# musical-plant.net
KiCad netlist of a schematic drawn in EAGLE
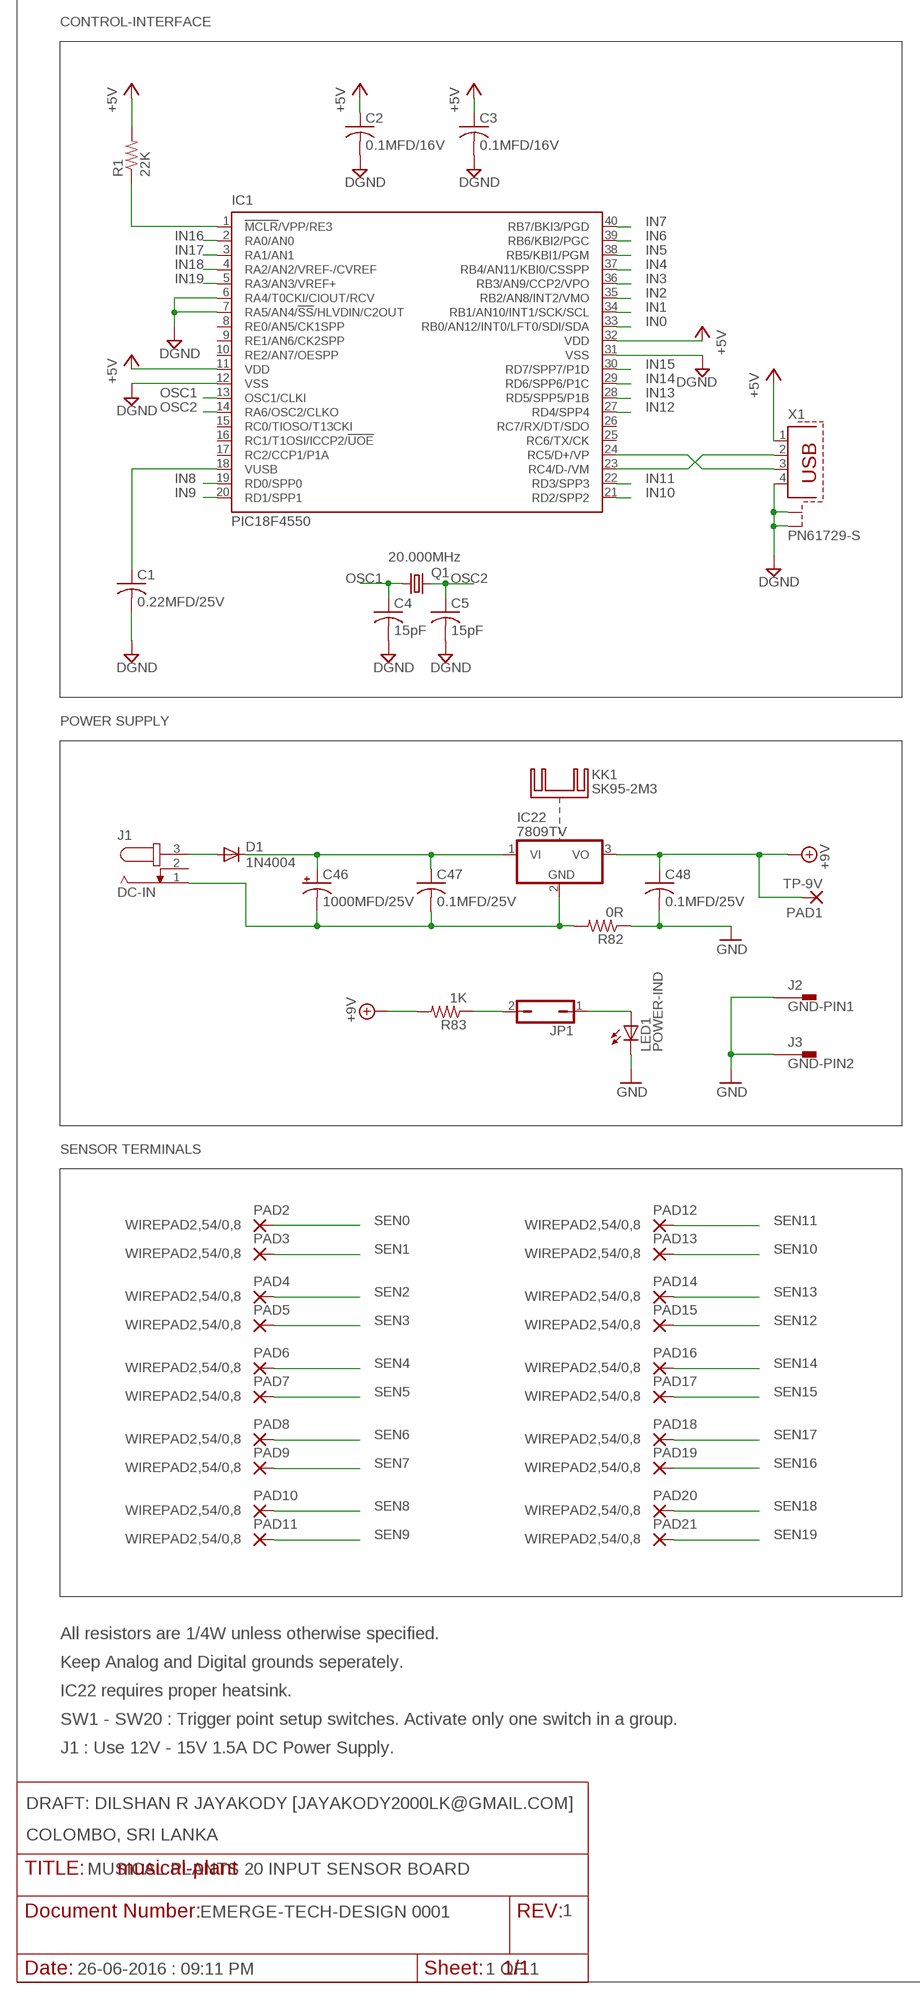
[diagram p0: schematic, sheet 1, part 1 of 2]
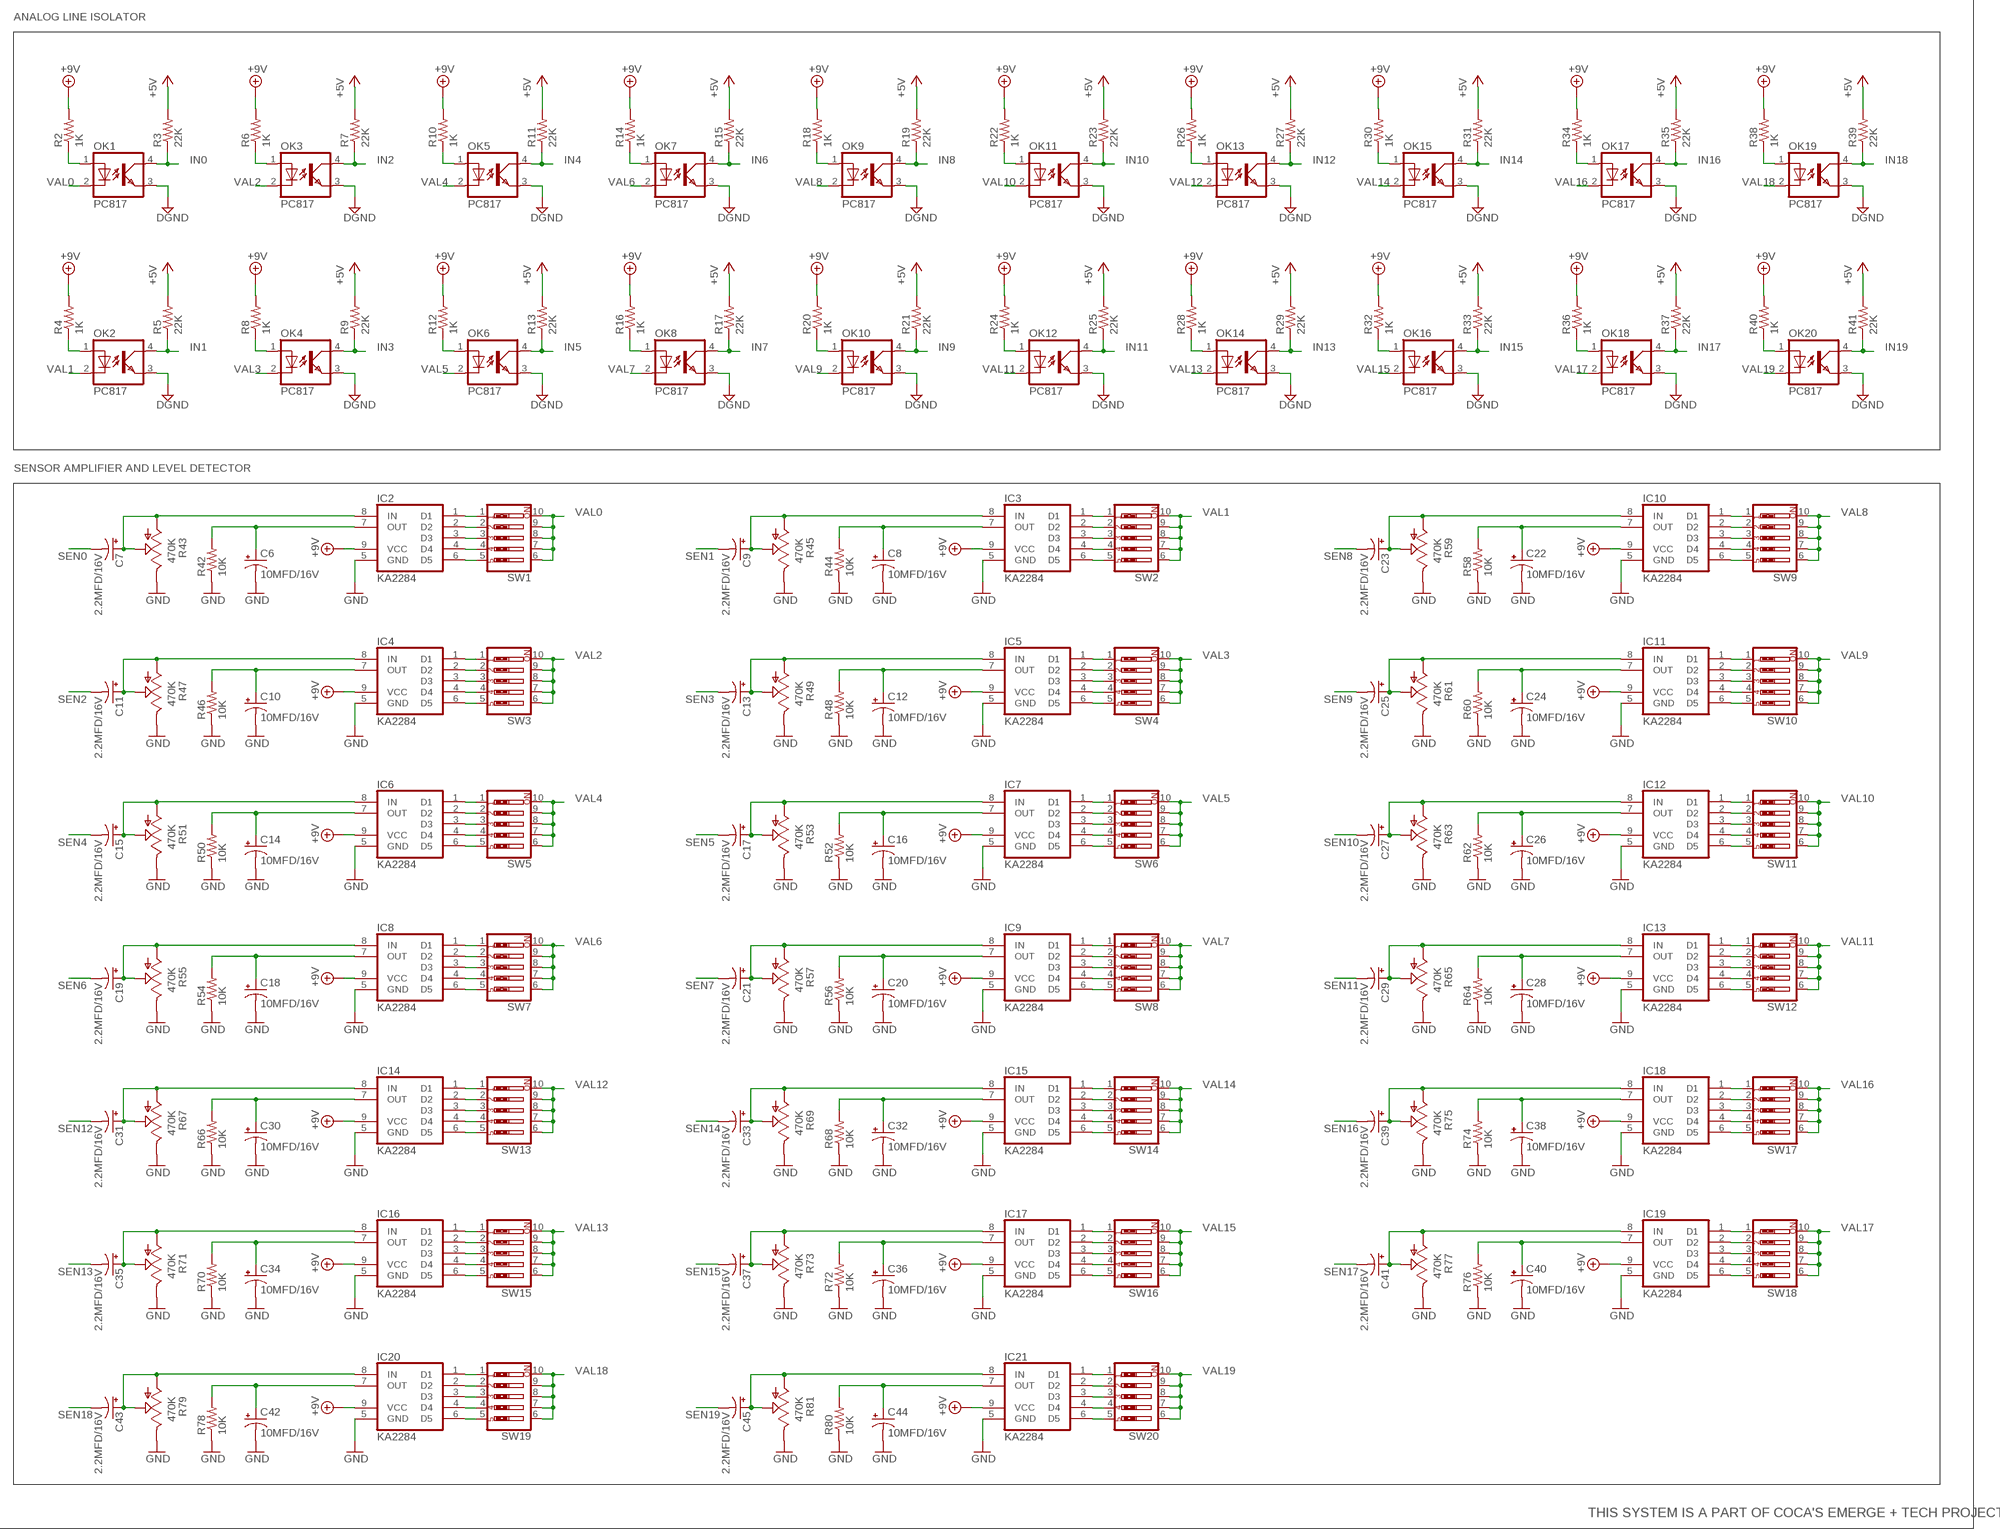
[diagram p1: schematic, sheet 1, part 2 of 2]

(export (version "E")
  (design (tool "Eeschema 10.0.6"))
  (components
    (comp (ref "C1")
      (value "0.22MFD/25V")
      (footprint "eagle-import:C075-052X106")
      (libsource (lib "eagle-import") (part "C-US075-052X106"))
    )
    (comp (ref "C2")
      (value "0.1MFD/16V")
      (footprint "eagle-import:C050-030X075")
      (libsource (lib "eagle-import") (part "C-US050-030X075"))
    )
    (comp (ref "C3")
      (value "0.1MFD/16V")
      (footprint "eagle-import:C050-030X075")
      (libsource (lib "eagle-import") (part "C-US050-030X075"))
    )
    (comp (ref "C4")
      (value "15pF")
      (footprint "eagle-import:C025-025X050")
      (libsource (lib "eagle-import") (part "C-US025-025X050"))
    )
    (comp (ref "C5")
      (value "15pF")
      (footprint "eagle-import:C025-025X050")
      (libsource (lib "eagle-import") (part "C-US025-025X050"))
    )
    (comp (ref "C6")
      (value "10MFD/16V")
      (footprint "eagle-import:E2,5-6E")
      (libsource (lib "eagle-import") (part "CPOL-USE2,5-6E"))
    )
    (comp (ref "C7")
      (value "2.2MFD/16V")
      (footprint "eagle-import:E2,5-6E")
      (libsource (lib "eagle-import") (part "CPOL-USE2,5-6E"))
    )
    (comp (ref "C8")
      (value "10MFD/16V")
      (footprint "eagle-import:E2,5-6E")
      (libsource (lib "eagle-import") (part "CPOL-USE2,5-6E"))
    )
    (comp (ref "C9")
      (value "2.2MFD/16V")
      (footprint "eagle-import:E2,5-6E")
      (libsource (lib "eagle-import") (part "CPOL-USE2,5-6E"))
    )
    (comp (ref "C10")
      (value "10MFD/16V")
      (footprint "eagle-import:E2,5-6E")
      (libsource (lib "eagle-import") (part "CPOL-USE2,5-6E"))
    )
    (comp (ref "C11")
      (value "2.2MFD/16V")
      (footprint "eagle-import:E2,5-6E")
      (libsource (lib "eagle-import") (part "CPOL-USE2,5-6E"))
    )
    (comp (ref "C12")
      (value "10MFD/16V")
      (footprint "eagle-import:E2,5-6E")
      (libsource (lib "eagle-import") (part "CPOL-USE2,5-6E"))
    )
    (comp (ref "C13")
      (value "2.2MFD/16V")
      (footprint "eagle-import:E2,5-6E")
      (libsource (lib "eagle-import") (part "CPOL-USE2,5-6E"))
    )
    (comp (ref "C14")
      (value "10MFD/16V")
      (footprint "eagle-import:E2,5-6E")
      (libsource (lib "eagle-import") (part "CPOL-USE2,5-6E"))
    )
    (comp (ref "C15")
      (value "2.2MFD/16V")
      (footprint "eagle-import:E2,5-6E")
      (libsource (lib "eagle-import") (part "CPOL-USE2,5-6E"))
    )
    (comp (ref "C16")
      (value "10MFD/16V")
      (footprint "eagle-import:E2,5-6E")
      (libsource (lib "eagle-import") (part "CPOL-USE2,5-6E"))
    )
    (comp (ref "C17")
      (value "2.2MFD/16V")
      (footprint "eagle-import:E2,5-6E")
      (libsource (lib "eagle-import") (part "CPOL-USE2,5-6E"))
    )
    (comp (ref "C18")
      (value "10MFD/16V")
      (footprint "eagle-import:E2,5-6E")
      (libsource (lib "eagle-import") (part "CPOL-USE2,5-6E"))
    )
    (comp (ref "C19")
      (value "2.2MFD/16V")
      (footprint "eagle-import:E2,5-6E")
      (libsource (lib "eagle-import") (part "CPOL-USE2,5-6E"))
    )
    (comp (ref "C20")
      (value "10MFD/16V")
      (footprint "eagle-import:E2,5-6E")
      (libsource (lib "eagle-import") (part "CPOL-USE2,5-6E"))
    )
    (comp (ref "C21")
      (value "2.2MFD/16V")
      (footprint "eagle-import:E2,5-6E")
      (libsource (lib "eagle-import") (part "CPOL-USE2,5-6E"))
    )
    (comp (ref "C22")
      (value "10MFD/16V")
      (footprint "eagle-import:E2,5-6E")
      (libsource (lib "eagle-import") (part "CPOL-USE2,5-6E"))
    )
    (comp (ref "C23")
      (value "2.2MFD/16V")
      (footprint "eagle-import:E2,5-6E")
      (libsource (lib "eagle-import") (part "CPOL-USE2,5-6E"))
    )
    (comp (ref "C24")
      (value "10MFD/16V")
      (footprint "eagle-import:E2,5-6E")
      (libsource (lib "eagle-import") (part "CPOL-USE2,5-6E"))
    )
    (comp (ref "C25")
      (value "2.2MFD/16V")
      (footprint "eagle-import:E2,5-6E")
      (libsource (lib "eagle-import") (part "CPOL-USE2,5-6E"))
    )
    (comp (ref "C26")
      (value "10MFD/16V")
      (footprint "eagle-import:E2,5-6E")
      (libsource (lib "eagle-import") (part "CPOL-USE2,5-6E"))
    )
    (comp (ref "C27")
      (value "2.2MFD/16V")
      (footprint "eagle-import:E2,5-6E")
      (libsource (lib "eagle-import") (part "CPOL-USE2,5-6E"))
    )
    (comp (ref "C28")
      (value "10MFD/16V")
      (footprint "eagle-import:E2,5-6E")
      (libsource (lib "eagle-import") (part "CPOL-USE2,5-6E"))
    )
    (comp (ref "C29")
      (value "2.2MFD/16V")
      (footprint "eagle-import:E2,5-6E")
      (libsource (lib "eagle-import") (part "CPOL-USE2,5-6E"))
    )
    (comp (ref "C30")
      (value "10MFD/16V")
      (footprint "eagle-import:E2,5-6E")
      (libsource (lib "eagle-import") (part "CPOL-USE2,5-6E"))
    )
    (comp (ref "C31")
      (value "2.2MFD/16V")
      (footprint "eagle-import:E2,5-6E")
      (libsource (lib "eagle-import") (part "CPOL-USE2,5-6E"))
    )
    (comp (ref "C32")
      (value "10MFD/16V")
      (footprint "eagle-import:E2,5-6E")
      (libsource (lib "eagle-import") (part "CPOL-USE2,5-6E"))
    )
    (comp (ref "C33")
      (value "2.2MFD/16V")
      (footprint "eagle-import:E2,5-6E")
      (libsource (lib "eagle-import") (part "CPOL-USE2,5-6E"))
    )
    (comp (ref "C34")
      (value "10MFD/16V")
      (footprint "eagle-import:E2,5-6E")
      (libsource (lib "eagle-import") (part "CPOL-USE2,5-6E"))
    )
    (comp (ref "C35")
      (value "2.2MFD/16V")
      (footprint "eagle-import:E2,5-6E")
      (libsource (lib "eagle-import") (part "CPOL-USE2,5-6E"))
    )
    (comp (ref "C36")
      (value "10MFD/16V")
      (footprint "eagle-import:E2,5-6E")
      (libsource (lib "eagle-import") (part "CPOL-USE2,5-6E"))
    )
    (comp (ref "C37")
      (value "2.2MFD/16V")
      (footprint "eagle-import:E2,5-6E")
      (libsource (lib "eagle-import") (part "CPOL-USE2,5-6E"))
    )
    (comp (ref "C38")
      (value "10MFD/16V")
      (footprint "eagle-import:E2,5-6E")
      (libsource (lib "eagle-import") (part "CPOL-USE2,5-6E"))
    )
    (comp (ref "C39")
      (value "2.2MFD/16V")
      (footprint "eagle-import:E2,5-6E")
      (libsource (lib "eagle-import") (part "CPOL-USE2,5-6E"))
    )
    (comp (ref "C40")
      (value "10MFD/16V")
      (footprint "eagle-import:E2,5-6E")
      (libsource (lib "eagle-import") (part "CPOL-USE2,5-6E"))
    )
    (comp (ref "C41")
      (value "2.2MFD/16V")
      (footprint "eagle-import:E2,5-6E")
      (libsource (lib "eagle-import") (part "CPOL-USE2,5-6E"))
    )
    (comp (ref "C42")
      (value "10MFD/16V")
      (footprint "eagle-import:E2,5-6E")
      (libsource (lib "eagle-import") (part "CPOL-USE2,5-6E"))
    )
    (comp (ref "C43")
      (value "2.2MFD/16V")
      (footprint "eagle-import:E2,5-6E")
      (libsource (lib "eagle-import") (part "CPOL-USE2,5-6E"))
    )
    (comp (ref "C44")
      (value "10MFD/16V")
      (footprint "eagle-import:E2,5-6E")
      (libsource (lib "eagle-import") (part "CPOL-USE2,5-6E"))
    )
    (comp (ref "C45")
      (value "2.2MFD/16V")
      (footprint "eagle-import:E2,5-6E")
      (libsource (lib "eagle-import") (part "CPOL-USE2,5-6E"))
    )
    (comp (ref "C46")
      (value "1000MFD/25V")
      (footprint "eagle-import:E5-13")
      (libsource (lib "eagle-import") (part "CPOL-USE5-13"))
    )
    (comp (ref "C47")
      (value "0.1MFD/25V")
      (footprint "eagle-import:C075-052X106")
      (libsource (lib "eagle-import") (part "C-US075-052X106"))
    )
    (comp (ref "C48")
      (value "0.1MFD/25V")
      (footprint "eagle-import:C075-052X106")
      (libsource (lib "eagle-import") (part "C-US075-052X106"))
    )
    (comp (ref "D1")
      (value "1N4004")
      (footprint "eagle-import:DO41-10")
      (libsource (lib "eagle-import") (part "1N4004"))
    )
    (comp (ref "IC1")
      (value "PIC18F4550")
      (footprint "eagle-import:DIL40")
      (fields (field (name "MF") "MICROCHIP") (field (name "MPN") "PIC18F4550-I/P"))
      (libsource (lib "eagle-import") (part "PIC18F4_40550"))
    )
    (comp (ref "IC2")
      (value "KA2284")
      (footprint "eagle-import:SIP-9")
      (libsource (lib "eagle-import") (part "KA2284"))
    )
    (comp (ref "IC3")
      (value "KA2284")
      (footprint "eagle-import:SIP-9")
      (libsource (lib "eagle-import") (part "KA2284"))
    )
    (comp (ref "IC4")
      (value "KA2284")
      (footprint "eagle-import:SIP-9")
      (libsource (lib "eagle-import") (part "KA2284"))
    )
    (comp (ref "IC5")
      (value "KA2284")
      (footprint "eagle-import:SIP-9")
      (libsource (lib "eagle-import") (part "KA2284"))
    )
    (comp (ref "IC6")
      (value "KA2284")
      (footprint "eagle-import:SIP-9")
      (libsource (lib "eagle-import") (part "KA2284"))
    )
    (comp (ref "IC7")
      (value "KA2284")
      (footprint "eagle-import:SIP-9")
      (libsource (lib "eagle-import") (part "KA2284"))
    )
    (comp (ref "IC8")
      (value "KA2284")
      (footprint "eagle-import:SIP-9")
      (libsource (lib "eagle-import") (part "KA2284"))
    )
    (comp (ref "IC9")
      (value "KA2284")
      (footprint "eagle-import:SIP-9")
      (libsource (lib "eagle-import") (part "KA2284"))
    )
    (comp (ref "IC10")
      (value "KA2284")
      (footprint "eagle-import:SIP-9")
      (libsource (lib "eagle-import") (part "KA2284"))
    )
    (comp (ref "IC11")
      (value "KA2284")
      (footprint "eagle-import:SIP-9")
      (libsource (lib "eagle-import") (part "KA2284"))
    )
    (comp (ref "IC12")
      (value "KA2284")
      (footprint "eagle-import:SIP-9")
      (libsource (lib "eagle-import") (part "KA2284"))
    )
    (comp (ref "IC13")
      (value "KA2284")
      (footprint "eagle-import:SIP-9")
      (libsource (lib "eagle-import") (part "KA2284"))
    )
    (comp (ref "IC14")
      (value "KA2284")
      (footprint "eagle-import:SIP-9")
      (libsource (lib "eagle-import") (part "KA2284"))
    )
    (comp (ref "IC15")
      (value "KA2284")
      (footprint "eagle-import:SIP-9")
      (libsource (lib "eagle-import") (part "KA2284"))
    )
    (comp (ref "IC16")
      (value "KA2284")
      (footprint "eagle-import:SIP-9")
      (libsource (lib "eagle-import") (part "KA2284"))
    )
    (comp (ref "IC17")
      (value "KA2284")
      (footprint "eagle-import:SIP-9")
      (libsource (lib "eagle-import") (part "KA2284"))
    )
    (comp (ref "IC18")
      (value "KA2284")
      (footprint "eagle-import:SIP-9")
      (libsource (lib "eagle-import") (part "KA2284"))
    )
    (comp (ref "IC19")
      (value "KA2284")
      (footprint "eagle-import:SIP-9")
      (libsource (lib "eagle-import") (part "KA2284"))
    )
    (comp (ref "IC20")
      (value "KA2284")
      (footprint "eagle-import:SIP-9")
      (libsource (lib "eagle-import") (part "KA2284"))
    )
    (comp (ref "IC21")
      (value "KA2284")
      (footprint "eagle-import:SIP-9")
      (libsource (lib "eagle-import") (part "KA2284"))
    )
    (comp (ref "IC22")
      (value "7809TV")
      (footprint "eagle-import:TO220V")
      (libsource (lib "eagle-import") (part "78TV12"))
    )
    (comp (ref "J1")
      (value "DC-IN")
      (footprint "eagle-import:SPC4078")
      (libsource (lib "eagle-import") (part "JACK-PLUG1"))
    )
    (comp (ref "J2")
      (value "GND-PIN1")
      (footprint "eagle-import:F061.080")
      (libsource (lib "eagle-import") (part "PIN2F061.080"))
    )
    (comp (ref "J3")
      (value "GND-PIN2")
      (footprint "eagle-import:F061.080")
      (libsource (lib "eagle-import") (part "PIN2F061.080"))
    )
    (comp (ref "JP1")
      (value "JP1Q")
      (footprint "eagle-import:JP1")
      (libsource (lib "eagle-import") (part "JP1Q"))
    )
    (comp (ref "KK1")
      (value "SK95-2M3")
      (footprint "eagle-import:SK95-2M3")
      (libsource (lib "eagle-import") (part "SK95-2M3"))
    )
    (comp (ref "LED1")
      (value "POWER-IND")
      (footprint "eagle-import:LED3MM")
      (libsource (lib "eagle-import") (part "LED3MM"))
    )
    (comp (ref "OK1")
      (value "PC817")
      (footprint "eagle-import:DIL04")
      (fields (field (name "MPN") "PC817X4J000F"))
      (libsource (lib "eagle-import") (part "PC817"))
    )
    (comp (ref "OK2")
      (value "PC817")
      (footprint "eagle-import:DIL04")
      (fields (field (name "MPN") "PC817X4J000F"))
      (libsource (lib "eagle-import") (part "PC817"))
    )
    (comp (ref "OK3")
      (value "PC817")
      (footprint "eagle-import:DIL04")
      (fields (field (name "MPN") "PC817X4J000F"))
      (libsource (lib "eagle-import") (part "PC817"))
    )
    (comp (ref "OK4")
      (value "PC817")
      (footprint "eagle-import:DIL04")
      (fields (field (name "MPN") "PC817X4J000F"))
      (libsource (lib "eagle-import") (part "PC817"))
    )
    (comp (ref "OK5")
      (value "PC817")
      (footprint "eagle-import:DIL04")
      (fields (field (name "MPN") "PC817X4J000F"))
      (libsource (lib "eagle-import") (part "PC817"))
    )
    (comp (ref "OK6")
      (value "PC817")
      (footprint "eagle-import:DIL04")
      (fields (field (name "MPN") "PC817X4J000F"))
      (libsource (lib "eagle-import") (part "PC817"))
    )
    (comp (ref "OK7")
      (value "PC817")
      (footprint "eagle-import:DIL04")
      (fields (field (name "MPN") "PC817X4J000F"))
      (libsource (lib "eagle-import") (part "PC817"))
    )
    (comp (ref "OK8")
      (value "PC817")
      (footprint "eagle-import:DIL04")
      (fields (field (name "MPN") "PC817X4J000F"))
      (libsource (lib "eagle-import") (part "PC817"))
    )
    (comp (ref "OK9")
      (value "PC817")
      (footprint "eagle-import:DIL04")
      (fields (field (name "MPN") "PC817X4J000F"))
      (libsource (lib "eagle-import") (part "PC817"))
    )
    (comp (ref "OK10")
      (value "PC817")
      (footprint "eagle-import:DIL04")
      (fields (field (name "MPN") "PC817X4J000F"))
      (libsource (lib "eagle-import") (part "PC817"))
    )
    (comp (ref "OK11")
      (value "PC817")
      (footprint "eagle-import:DIL04")
      (fields (field (name "MPN") "PC817X4J000F"))
      (libsource (lib "eagle-import") (part "PC817"))
    )
    (comp (ref "OK12")
      (value "PC817")
      (footprint "eagle-import:DIL04")
      (fields (field (name "MPN") "PC817X4J000F"))
      (libsource (lib "eagle-import") (part "PC817"))
    )
    (comp (ref "OK13")
      (value "PC817")
      (footprint "eagle-import:DIL04")
      (fields (field (name "MPN") "PC817X4J000F"))
      (libsource (lib "eagle-import") (part "PC817"))
    )
    (comp (ref "OK14")
      (value "PC817")
      (footprint "eagle-import:DIL04")
      (fields (field (name "MPN") "PC817X4J000F"))
      (libsource (lib "eagle-import") (part "PC817"))
    )
    (comp (ref "OK15")
      (value "PC817")
      (footprint "eagle-import:DIL04")
      (fields (field (name "MPN") "PC817X4J000F"))
      (libsource (lib "eagle-import") (part "PC817"))
    )
    (comp (ref "OK16")
      (value "PC817")
      (footprint "eagle-import:DIL04")
      (fields (field (name "MPN") "PC817X4J000F"))
      (libsource (lib "eagle-import") (part "PC817"))
    )
    (comp (ref "OK17")
      (value "PC817")
      (footprint "eagle-import:DIL04")
      (fields (field (name "MPN") "PC817X4J000F"))
      (libsource (lib "eagle-import") (part "PC817"))
    )
    (comp (ref "OK18")
      (value "PC817")
      (footprint "eagle-import:DIL04")
      (fields (field (name "MPN") "PC817X4J000F"))
      (libsource (lib "eagle-import") (part "PC817"))
    )
    (comp (ref "OK19")
      (value "PC817")
      (footprint "eagle-import:DIL04")
      (fields (field (name "MPN") "PC817X4J000F"))
      (libsource (lib "eagle-import") (part "PC817"))
    )
    (comp (ref "OK20")
      (value "PC817")
      (footprint "eagle-import:DIL04")
      (fields (field (name "MPN") "PC817X4J000F"))
      (libsource (lib "eagle-import") (part "PC817"))
    )
    (comp (ref "PAD1")
      (value "TP-9V")
      (footprint "eagle-import:2,15_1,0")
      (libsource (lib "eagle-import") (part "WIREPAD2,15/1,0"))
    )
    (comp (ref "PAD2")
      (value "WIREPAD2,54/0,8")
      (footprint "eagle-import:2,54_0,8")
      (libsource (lib "eagle-import") (part "WIREPAD2,54/0,8"))
    )
    (comp (ref "PAD3")
      (value "WIREPAD2,54/0,8")
      (footprint "eagle-import:2,54_0,8")
      (libsource (lib "eagle-import") (part "WIREPAD2,54/0,8"))
    )
    (comp (ref "PAD4")
      (value "WIREPAD2,54/0,8")
      (footprint "eagle-import:2,54_0,8")
      (libsource (lib "eagle-import") (part "WIREPAD2,54/0,8"))
    )
    (comp (ref "PAD5")
      (value "WIREPAD2,54/0,8")
      (footprint "eagle-import:2,54_0,8")
      (libsource (lib "eagle-import") (part "WIREPAD2,54/0,8"))
    )
    (comp (ref "PAD6")
      (value "WIREPAD2,54/0,8")
      (footprint "eagle-import:2,54_0,8")
      (libsource (lib "eagle-import") (part "WIREPAD2,54/0,8"))
    )
    (comp (ref "PAD7")
      (value "WIREPAD2,54/0,8")
      (footprint "eagle-import:2,54_0,8")
      (libsource (lib "eagle-import") (part "WIREPAD2,54/0,8"))
    )
    (comp (ref "PAD8")
      (value "WIREPAD2,54/0,8")
      (footprint "eagle-import:2,54_0,8")
      (libsource (lib "eagle-import") (part "WIREPAD2,54/0,8"))
    )
    (comp (ref "PAD9")
      (value "WIREPAD2,54/0,8")
      (footprint "eagle-import:2,54_0,8")
      (libsource (lib "eagle-import") (part "WIREPAD2,54/0,8"))
    )
    (comp (ref "PAD10")
      (value "WIREPAD2,54/0,8")
      (footprint "eagle-import:2,54_0,8")
      (libsource (lib "eagle-import") (part "WIREPAD2,54/0,8"))
    )
    (comp (ref "PAD11")
      (value "WIREPAD2,54/0,8")
      (footprint "eagle-import:2,54_0,8")
      (libsource (lib "eagle-import") (part "WIREPAD2,54/0,8"))
    )
    (comp (ref "PAD12")
      (value "WIREPAD2,54/0,8")
      (footprint "eagle-import:2,54_0,8")
      (libsource (lib "eagle-import") (part "WIREPAD2,54/0,8"))
    )
    (comp (ref "PAD13")
      (value "WIREPAD2,54/0,8")
      (footprint "eagle-import:2,54_0,8")
      (libsource (lib "eagle-import") (part "WIREPAD2,54/0,8"))
    )
    (comp (ref "PAD14")
      (value "WIREPAD2,54/0,8")
      (footprint "eagle-import:2,54_0,8")
      (libsource (lib "eagle-import") (part "WIREPAD2,54/0,8"))
    )
    (comp (ref "PAD15")
      (value "WIREPAD2,54/0,8")
      (footprint "eagle-import:2,54_0,8")
      (libsource (lib "eagle-import") (part "WIREPAD2,54/0,8"))
    )
    (comp (ref "PAD16")
      (value "WIREPAD2,54/0,8")
      (footprint "eagle-import:2,54_0,8")
      (libsource (lib "eagle-import") (part "WIREPAD2,54/0,8"))
    )
    (comp (ref "PAD17")
      (value "WIREPAD2,54/0,8")
      (footprint "eagle-import:2,54_0,8")
      (libsource (lib "eagle-import") (part "WIREPAD2,54/0,8"))
    )
    (comp (ref "PAD18")
      (value "WIREPAD2,54/0,8")
      (footprint "eagle-import:2,54_0,8")
      (libsource (lib "eagle-import") (part "WIREPAD2,54/0,8"))
    )
    (comp (ref "PAD19")
      (value "WIREPAD2,54/0,8")
      (footprint "eagle-import:2,54_0,8")
      (libsource (lib "eagle-import") (part "WIREPAD2,54/0,8"))
    )
    (comp (ref "PAD20")
      (value "WIREPAD2,54/0,8")
      (footprint "eagle-import:2,54_0,8")
      (libsource (lib "eagle-import") (part "WIREPAD2,54/0,8"))
    )
    (comp (ref "PAD21")
      (value "WIREPAD2,54/0,8")
      (footprint "eagle-import:2,54_0,8")
      (libsource (lib "eagle-import") (part "WIREPAD2,54/0,8"))
    )
    (comp (ref "Q1")
      (value "20.000MHz")
      (footprint "eagle-import:HC49_S")
      (libsource (lib "eagle-import") (part "CRYSTALHC49S"))
    )
    (comp (ref "R1")
      (value "22K")
      (footprint "eagle-import:0207_10")
      (libsource (lib "eagle-import") (part "R-US_0207/10"))
    )
    (comp (ref "R2")
      (value "1K")
      (footprint "eagle-import:0207_10")
      (libsource (lib "eagle-import") (part "R-US_0207/10"))
    )
    (comp (ref "R3")
      (value "22K")
      (footprint "eagle-import:0207_15")
      (libsource (lib "eagle-import") (part "R-US_0207/15"))
    )
    (comp (ref "R4")
      (value "1K")
      (footprint "eagle-import:0207_10")
      (libsource (lib "eagle-import") (part "R-US_0207/10"))
    )
    (comp (ref "R5")
      (value "22K")
      (footprint "eagle-import:0207_15")
      (libsource (lib "eagle-import") (part "R-US_0207/15"))
    )
    (comp (ref "R6")
      (value "1K")
      (footprint "eagle-import:0207_10")
      (libsource (lib "eagle-import") (part "R-US_0207/10"))
    )
    (comp (ref "R7")
      (value "22K")
      (footprint "eagle-import:0207_15")
      (libsource (lib "eagle-import") (part "R-US_0207/15"))
    )
    (comp (ref "R8")
      (value "1K")
      (footprint "eagle-import:0207_10")
      (libsource (lib "eagle-import") (part "R-US_0207/10"))
    )
    (comp (ref "R9")
      (value "22K")
      (footprint "eagle-import:0207_15")
      (libsource (lib "eagle-import") (part "R-US_0207/15"))
    )
    (comp (ref "R10")
      (value "1K")
      (footprint "eagle-import:0207_10")
      (libsource (lib "eagle-import") (part "R-US_0207/10"))
    )
    (comp (ref "R11")
      (value "22K")
      (footprint "eagle-import:0207_15")
      (libsource (lib "eagle-import") (part "R-US_0207/15"))
    )
    (comp (ref "R12")
      (value "1K")
      (footprint "eagle-import:0207_10")
      (libsource (lib "eagle-import") (part "R-US_0207/10"))
    )
    (comp (ref "R13")
      (value "22K")
      (footprint "eagle-import:0207_15")
      (libsource (lib "eagle-import") (part "R-US_0207/15"))
    )
    (comp (ref "R14")
      (value "1K")
      (footprint "eagle-import:0207_10")
      (libsource (lib "eagle-import") (part "R-US_0207/10"))
    )
    (comp (ref "R15")
      (value "22K")
      (footprint "eagle-import:0207_15")
      (libsource (lib "eagle-import") (part "R-US_0207/15"))
    )
    (comp (ref "R16")
      (value "1K")
      (footprint "eagle-import:0207_10")
      (libsource (lib "eagle-import") (part "R-US_0207/10"))
    )
    (comp (ref "R17")
      (value "22K")
      (footprint "eagle-import:0207_15")
      (libsource (lib "eagle-import") (part "R-US_0207/15"))
    )
    (comp (ref "R18")
      (value "1K")
      (footprint "eagle-import:0207_10")
      (libsource (lib "eagle-import") (part "R-US_0207/10"))
    )
    (comp (ref "R19")
      (value "22K")
      (footprint "eagle-import:0207_15")
      (libsource (lib "eagle-import") (part "R-US_0207/15"))
    )
    (comp (ref "R20")
      (value "1K")
      (footprint "eagle-import:0207_10")
      (libsource (lib "eagle-import") (part "R-US_0207/10"))
    )
    (comp (ref "R21")
      (value "22K")
      (footprint "eagle-import:0207_15")
      (libsource (lib "eagle-import") (part "R-US_0207/15"))
    )
    (comp (ref "R22")
      (value "1K")
      (footprint "eagle-import:0207_10")
      (libsource (lib "eagle-import") (part "R-US_0207/10"))
    )
    (comp (ref "R23")
      (value "22K")
      (footprint "eagle-import:0207_15")
      (libsource (lib "eagle-import") (part "R-US_0207/15"))
    )
    (comp (ref "R24")
      (value "1K")
      (footprint "eagle-import:0207_10")
      (libsource (lib "eagle-import") (part "R-US_0207/10"))
    )
    (comp (ref "R25")
      (value "22K")
      (footprint "eagle-import:0207_15")
      (libsource (lib "eagle-import") (part "R-US_0207/15"))
    )
    (comp (ref "R26")
      (value "1K")
      (footprint "eagle-import:0207_10")
      (libsource (lib "eagle-import") (part "R-US_0207/10"))
    )
    (comp (ref "R27")
      (value "22K")
      (footprint "eagle-import:0207_15")
      (libsource (lib "eagle-import") (part "R-US_0207/15"))
    )
    (comp (ref "R28")
      (value "1K")
      (footprint "eagle-import:0207_10")
      (libsource (lib "eagle-import") (part "R-US_0207/10"))
    )
    (comp (ref "R29")
      (value "22K")
      (footprint "eagle-import:0207_15")
      (libsource (lib "eagle-import") (part "R-US_0207/15"))
    )
    (comp (ref "R30")
      (value "1K")
      (footprint "eagle-import:0207_10")
      (libsource (lib "eagle-import") (part "R-US_0207/10"))
    )
    (comp (ref "R31")
      (value "22K")
      (footprint "eagle-import:0207_15")
      (libsource (lib "eagle-import") (part "R-US_0207/15"))
    )
    (comp (ref "R32")
      (value "1K")
      (footprint "eagle-import:0207_10")
      (libsource (lib "eagle-import") (part "R-US_0207/10"))
    )
    (comp (ref "R33")
      (value "22K")
      (footprint "eagle-import:0207_15")
      (libsource (lib "eagle-import") (part "R-US_0207/15"))
    )
    (comp (ref "R34")
      (value "1K")
      (footprint "eagle-import:0207_10")
      (libsource (lib "eagle-import") (part "R-US_0207/10"))
    )
    (comp (ref "R35")
      (value "22K")
      (footprint "eagle-import:0207_15")
      (libsource (lib "eagle-import") (part "R-US_0207/15"))
    )
    (comp (ref "R36")
      (value "1K")
      (footprint "eagle-import:0207_10")
      (libsource (lib "eagle-import") (part "R-US_0207/10"))
    )
    (comp (ref "R37")
      (value "22K")
      (footprint "eagle-import:0207_15")
      (libsource (lib "eagle-import") (part "R-US_0207/15"))
    )
    (comp (ref "R38")
      (value "1K")
      (footprint "eagle-import:0207_10")
      (libsource (lib "eagle-import") (part "R-US_0207/10"))
    )
    (comp (ref "R39")
      (value "22K")
      (footprint "eagle-import:0207_15")
      (libsource (lib "eagle-import") (part "R-US_0207/15"))
    )
    (comp (ref "R40")
      (value "1K")
      (footprint "eagle-import:0207_10")
      (libsource (lib "eagle-import") (part "R-US_0207/10"))
    )
    (comp (ref "R41")
      (value "22K")
      (footprint "eagle-import:0207_15")
      (libsource (lib "eagle-import") (part "R-US_0207/15"))
    )
    (comp (ref "R42")
      (value "10K")
      (footprint "eagle-import:0207_10")
      (libsource (lib "eagle-import") (part "R-US_0207/10"))
    )
    (comp (ref "R43")
      (value "470K")
      (footprint "eagle-import:RS3")
      (libsource (lib "eagle-import") (part "TRIM_US-RS3"))
    )
    (comp (ref "R44")
      (value "10K")
      (footprint "eagle-import:0207_10")
      (libsource (lib "eagle-import") (part "R-US_0207/10"))
    )
    (comp (ref "R45")
      (value "470K")
      (footprint "eagle-import:RS3")
      (libsource (lib "eagle-import") (part "TRIM_US-RS3"))
    )
    (comp (ref "R46")
      (value "10K")
      (footprint "eagle-import:0207_10")
      (libsource (lib "eagle-import") (part "R-US_0207/10"))
    )
    (comp (ref "R47")
      (value "470K")
      (footprint "eagle-import:RS3")
      (libsource (lib "eagle-import") (part "TRIM_US-RS3"))
    )
    (comp (ref "R48")
      (value "10K")
      (footprint "eagle-import:0207_10")
      (libsource (lib "eagle-import") (part "R-US_0207/10"))
    )
    (comp (ref "R49")
      (value "470K")
      (footprint "eagle-import:RS3")
      (libsource (lib "eagle-import") (part "TRIM_US-RS3"))
    )
    (comp (ref "R50")
      (value "10K")
      (footprint "eagle-import:0207_10")
      (libsource (lib "eagle-import") (part "R-US_0207/10"))
    )
    (comp (ref "R51")
      (value "470K")
      (footprint "eagle-import:RS3")
      (libsource (lib "eagle-import") (part "TRIM_US-RS3"))
    )
    (comp (ref "R52")
      (value "10K")
      (footprint "eagle-import:0207_10")
      (libsource (lib "eagle-import") (part "R-US_0207/10"))
    )
    (comp (ref "R53")
      (value "470K")
      (footprint "eagle-import:RS3")
      (libsource (lib "eagle-import") (part "TRIM_US-RS3"))
    )
    (comp (ref "R54")
      (value "10K")
      (footprint "eagle-import:0207_10")
      (libsource (lib "eagle-import") (part "R-US_0207/10"))
    )
    (comp (ref "R55")
      (value "470K")
      (footprint "eagle-import:RS3")
      (libsource (lib "eagle-import") (part "TRIM_US-RS3"))
    )
    (comp (ref "R56")
      (value "10K")
      (footprint "eagle-import:0207_10")
      (libsource (lib "eagle-import") (part "R-US_0207/10"))
    )
    (comp (ref "R57")
      (value "470K")
      (footprint "eagle-import:RS3")
      (libsource (lib "eagle-import") (part "TRIM_US-RS3"))
    )
    (comp (ref "R58")
      (value "10K")
      (footprint "eagle-import:0207_10")
      (libsource (lib "eagle-import") (part "R-US_0207/10"))
    )
    (comp (ref "R59")
      (value "470K")
      (footprint "eagle-import:RS3")
      (libsource (lib "eagle-import") (part "TRIM_US-RS3"))
    )
    (comp (ref "R60")
      (value "10K")
      (footprint "eagle-import:0207_10")
      (libsource (lib "eagle-import") (part "R-US_0207/10"))
    )
    (comp (ref "R61")
      (value "470K")
      (footprint "eagle-import:RS3")
      (libsource (lib "eagle-import") (part "TRIM_US-RS3"))
    )
    (comp (ref "R62")
      (value "10K")
      (footprint "eagle-import:0207_10")
      (libsource (lib "eagle-import") (part "R-US_0207/10"))
    )
    (comp (ref "R63")
      (value "470K")
      (footprint "eagle-import:RS3")
      (libsource (lib "eagle-import") (part "TRIM_US-RS3"))
    )
    (comp (ref "R64")
      (value "10K")
      (footprint "eagle-import:0207_10")
      (libsource (lib "eagle-import") (part "R-US_0207/10"))
    )
    (comp (ref "R65")
      (value "470K")
      (footprint "eagle-import:RS3")
      (libsource (lib "eagle-import") (part "TRIM_US-RS3"))
    )
    (comp (ref "R66")
      (value "10K")
      (footprint "eagle-import:0207_10")
      (libsource (lib "eagle-import") (part "R-US_0207/10"))
    )
    (comp (ref "R67")
      (value "470K")
      (footprint "eagle-import:RS3")
      (libsource (lib "eagle-import") (part "TRIM_US-RS3"))
    )
    (comp (ref "R68")
      (value "10K")
      (footprint "eagle-import:0207_10")
      (libsource (lib "eagle-import") (part "R-US_0207/10"))
    )
    (comp (ref "R69")
      (value "470K")
      (footprint "eagle-import:RS3")
      (libsource (lib "eagle-import") (part "TRIM_US-RS3"))
    )
    (comp (ref "R70")
      (value "10K")
      (footprint "eagle-import:0207_10")
      (libsource (lib "eagle-import") (part "R-US_0207/10"))
    )
    (comp (ref "R71")
      (value "470K")
      (footprint "eagle-import:RS3")
      (libsource (lib "eagle-import") (part "TRIM_US-RS3"))
    )
    (comp (ref "R72")
      (value "10K")
      (footprint "eagle-import:0207_10")
      (libsource (lib "eagle-import") (part "R-US_0207/10"))
    )
    (comp (ref "R73")
      (value "470K")
      (footprint "eagle-import:RS3")
      (libsource (lib "eagle-import") (part "TRIM_US-RS3"))
    )
    (comp (ref "R74")
      (value "10K")
      (footprint "eagle-import:0207_10")
      (libsource (lib "eagle-import") (part "R-US_0207/10"))
    )
    (comp (ref "R75")
      (value "470K")
      (footprint "eagle-import:RS3")
      (libsource (lib "eagle-import") (part "TRIM_US-RS3"))
    )
    (comp (ref "R76")
      (value "10K")
      (footprint "eagle-import:0207_10")
      (libsource (lib "eagle-import") (part "R-US_0207/10"))
    )
    (comp (ref "R77")
      (value "470K")
      (footprint "eagle-import:RS3")
      (libsource (lib "eagle-import") (part "TRIM_US-RS3"))
    )
    (comp (ref "R78")
      (value "10K")
      (footprint "eagle-import:0207_10")
      (libsource (lib "eagle-import") (part "R-US_0207/10"))
    )
    (comp (ref "R79")
      (value "470K")
      (footprint "eagle-import:RS3")
      (libsource (lib "eagle-import") (part "TRIM_US-RS3"))
    )
    (comp (ref "R80")
      (value "10K")
      (footprint "eagle-import:0207_10")
      (libsource (lib "eagle-import") (part "R-US_0207/10"))
    )
    (comp (ref "R81")
      (value "470K")
      (footprint "eagle-import:RS3")
      (libsource (lib "eagle-import") (part "TRIM_US-RS3"))
    )
    (comp (ref "R82")
      (value "0R")
      (footprint "eagle-import:0207_10")
      (libsource (lib "eagle-import") (part "R-US_0207/10"))
    )
    (comp (ref "R83")
      (value "1K")
      (footprint "eagle-import:0207_10")
      (libsource (lib "eagle-import") (part "R-US_0207/10"))
    )
    (comp (ref "SW1")
      (value "SW_DIP-5")
      (footprint "eagle-import:EDG-05")
      (libsource (lib "eagle-import") (part "SW_DIP-5"))
    )
    (comp (ref "SW2")
      (value "SW_DIP-5")
      (footprint "eagle-import:EDG-05")
      (libsource (lib "eagle-import") (part "SW_DIP-5"))
    )
    (comp (ref "SW3")
      (value "SW_DIP-5")
      (footprint "eagle-import:EDG-05")
      (libsource (lib "eagle-import") (part "SW_DIP-5"))
    )
    (comp (ref "SW4")
      (value "SW_DIP-5")
      (footprint "eagle-import:EDG-05")
      (libsource (lib "eagle-import") (part "SW_DIP-5"))
    )
    (comp (ref "SW5")
      (value "SW_DIP-5")
      (footprint "eagle-import:EDG-05")
      (libsource (lib "eagle-import") (part "SW_DIP-5"))
    )
    (comp (ref "SW6")
      (value "SW_DIP-5")
      (footprint "eagle-import:EDG-05")
      (libsource (lib "eagle-import") (part "SW_DIP-5"))
    )
    (comp (ref "SW7")
      (value "SW_DIP-5")
      (footprint "eagle-import:EDG-05")
      (libsource (lib "eagle-import") (part "SW_DIP-5"))
    )
    (comp (ref "SW8")
      (value "SW_DIP-5")
      (footprint "eagle-import:EDG-05")
      (libsource (lib "eagle-import") (part "SW_DIP-5"))
    )
    (comp (ref "SW9")
      (value "SW_DIP-5")
      (footprint "eagle-import:EDG-05")
      (libsource (lib "eagle-import") (part "SW_DIP-5"))
    )
    (comp (ref "SW10")
      (value "SW_DIP-5")
      (footprint "eagle-import:EDG-05")
      (libsource (lib "eagle-import") (part "SW_DIP-5"))
    )
    (comp (ref "SW11")
      (value "SW_DIP-5")
      (footprint "eagle-import:EDG-05")
      (libsource (lib "eagle-import") (part "SW_DIP-5"))
    )
    (comp (ref "SW12")
      (value "SW_DIP-5")
      (footprint "eagle-import:EDG-05")
      (libsource (lib "eagle-import") (part "SW_DIP-5"))
    )
    (comp (ref "SW13")
      (value "SW_DIP-5")
      (footprint "eagle-import:EDG-05")
      (libsource (lib "eagle-import") (part "SW_DIP-5"))
    )
    (comp (ref "SW14")
      (value "SW_DIP-5")
      (footprint "eagle-import:EDG-05")
      (libsource (lib "eagle-import") (part "SW_DIP-5"))
    )
    (comp (ref "SW15")
      (value "SW_DIP-5")
      (footprint "eagle-import:EDG-05")
      (libsource (lib "eagle-import") (part "SW_DIP-5"))
    )
    (comp (ref "SW16")
      (value "SW_DIP-5")
      (footprint "eagle-import:EDG-05")
      (libsource (lib "eagle-import") (part "SW_DIP-5"))
    )
    (comp (ref "SW17")
      (value "SW_DIP-5")
      (footprint "eagle-import:EDG-05")
      (libsource (lib "eagle-import") (part "SW_DIP-5"))
    )
    (comp (ref "SW18")
      (value "SW_DIP-5")
      (footprint "eagle-import:EDG-05")
      (libsource (lib "eagle-import") (part "SW_DIP-5"))
    )
    (comp (ref "SW19")
      (value "SW_DIP-5")
      (footprint "eagle-import:EDG-05")
      (libsource (lib "eagle-import") (part "SW_DIP-5"))
    )
    (comp (ref "SW20")
      (value "SW_DIP-5")
      (footprint "eagle-import:EDG-05")
      (libsource (lib "eagle-import") (part "SW_DIP-5"))
    )
    (comp (ref "X1")
      (value "PN61729-S")
      (footprint "eagle-import:PN61729-S")
      (libsource (lib "eagle-import") (part "PN61729-S"))
    )
  )
  (nets
    (net (code "1") (name "+5V") (class "Default")
      (node (ref "C2") (pin "1") (pinfunction "1_1") (pintype "passive"))
      (node (ref "C3") (pin "1") (pinfunction "1_1") (pintype "passive"))
      (node (ref "IC1") (pin "11") (pinfunction "VDD_11") (pintype "power_in"))
      (node (ref "IC1") (pin "32") (pinfunction "VDD_32") (pintype "power_in"))
      (node (ref "R1") (pin "2") (pinfunction "2_2") (pintype "passive"))
      (node (ref "R11") (pin "2") (pinfunction "2_2") (pintype "passive"))
      (node (ref "R13") (pin "2") (pinfunction "2_2") (pintype "passive"))
      (node (ref "R15") (pin "2") (pinfunction "2_2") (pintype "passive"))
      (node (ref "R17") (pin "2") (pinfunction "2_2") (pintype "passive"))
      (node (ref "R19") (pin "2") (pinfunction "2_2") (pintype "passive"))
      (node (ref "R21") (pin "2") (pinfunction "2_2") (pintype "passive"))
      (node (ref "R23") (pin "2") (pinfunction "2_2") (pintype "passive"))
      (node (ref "R25") (pin "2") (pinfunction "2_2") (pintype "passive"))
      (node (ref "R27") (pin "2") (pinfunction "2_2") (pintype "passive"))
      (node (ref "R29") (pin "2") (pinfunction "2_2") (pintype "passive"))
      (node (ref "R3") (pin "2") (pinfunction "2_2") (pintype "passive"))
      (node (ref "R31") (pin "2") (pinfunction "2_2") (pintype "passive"))
      (node (ref "R33") (pin "2") (pinfunction "2_2") (pintype "passive"))
      (node (ref "R35") (pin "2") (pinfunction "2_2") (pintype "passive"))
      (node (ref "R37") (pin "2") (pinfunction "2_2") (pintype "passive"))
      (node (ref "R39") (pin "2") (pinfunction "2_2") (pintype "passive"))
      (node (ref "R41") (pin "2") (pinfunction "2_2") (pintype "passive"))
      (node (ref "R5") (pin "2") (pinfunction "2_2") (pintype "passive"))
      (node (ref "R7") (pin "2") (pinfunction "2_2") (pintype "passive"))
      (node (ref "R9") (pin "2") (pinfunction "2_2") (pintype "passive"))
      (node (ref "X1") (pin "1") (pinfunction "1_1") (pintype "passive"))
    )
    (net (code "2") (name "+9V") (class "Default")
      (node (ref "C48") (pin "1") (pinfunction "1_1") (pintype "passive"))
      (node (ref "IC10") (pin "9") (pinfunction "VCC_9") (pintype "input"))
      (node (ref "IC11") (pin "9") (pinfunction "VCC_9") (pintype "input"))
      (node (ref "IC12") (pin "9") (pinfunction "VCC_9") (pintype "input"))
      (node (ref "IC13") (pin "9") (pinfunction "VCC_9") (pintype "input"))
      (node (ref "IC14") (pin "9") (pinfunction "VCC_9") (pintype "input"))
      (node (ref "IC15") (pin "9") (pinfunction "VCC_9") (pintype "input"))
      (node (ref "IC16") (pin "9") (pinfunction "VCC_9") (pintype "input"))
      (node (ref "IC17") (pin "9") (pinfunction "VCC_9") (pintype "input"))
      (node (ref "IC18") (pin "9") (pinfunction "VCC_9") (pintype "input"))
      (node (ref "IC19") (pin "9") (pinfunction "VCC_9") (pintype "input"))
      (node (ref "IC2") (pin "9") (pinfunction "VCC_9") (pintype "input"))
      (node (ref "IC20") (pin "9") (pinfunction "VCC_9") (pintype "input"))
      (node (ref "IC21") (pin "9") (pinfunction "VCC_9") (pintype "input"))
      (node (ref "IC22") (pin "3") (pinfunction "VO_3") (pintype "passive"))
      (node (ref "IC3") (pin "9") (pinfunction "VCC_9") (pintype "input"))
      (node (ref "IC4") (pin "9") (pinfunction "VCC_9") (pintype "input"))
      (node (ref "IC5") (pin "9") (pinfunction "VCC_9") (pintype "input"))
      (node (ref "IC6") (pin "9") (pinfunction "VCC_9") (pintype "input"))
      (node (ref "IC7") (pin "9") (pinfunction "VCC_9") (pintype "input"))
      (node (ref "IC8") (pin "9") (pinfunction "VCC_9") (pintype "input"))
      (node (ref "IC9") (pin "9") (pinfunction "VCC_9") (pintype "input"))
      (node (ref "PAD1") (pin "1") (pinfunction "P_1") (pintype "passive"))
      (node (ref "R10") (pin "2") (pinfunction "2_2") (pintype "passive"))
      (node (ref "R12") (pin "2") (pinfunction "2_2") (pintype "passive"))
      (node (ref "R14") (pin "2") (pinfunction "2_2") (pintype "passive"))
      (node (ref "R16") (pin "2") (pinfunction "2_2") (pintype "passive"))
      (node (ref "R18") (pin "2") (pinfunction "2_2") (pintype "passive"))
      (node (ref "R2") (pin "2") (pinfunction "2_2") (pintype "passive"))
      (node (ref "R20") (pin "2") (pinfunction "2_2") (pintype "passive"))
      (node (ref "R22") (pin "2") (pinfunction "2_2") (pintype "passive"))
      (node (ref "R24") (pin "2") (pinfunction "2_2") (pintype "passive"))
      (node (ref "R26") (pin "2") (pinfunction "2_2") (pintype "passive"))
      (node (ref "R28") (pin "2") (pinfunction "2_2") (pintype "passive"))
      (node (ref "R30") (pin "2") (pinfunction "2_2") (pintype "passive"))
      (node (ref "R32") (pin "2") (pinfunction "2_2") (pintype "passive"))
      (node (ref "R34") (pin "2") (pinfunction "2_2") (pintype "passive"))
      (node (ref "R36") (pin "2") (pinfunction "2_2") (pintype "passive"))
      (node (ref "R38") (pin "2") (pinfunction "2_2") (pintype "passive"))
      (node (ref "R4") (pin "2") (pinfunction "2_2") (pintype "passive"))
      (node (ref "R40") (pin "2") (pinfunction "2_2") (pintype "passive"))
      (node (ref "R6") (pin "2") (pinfunction "2_2") (pintype "passive"))
      (node (ref "R8") (pin "2") (pinfunction "2_2") (pintype "passive"))
      (node (ref "R83") (pin "2") (pinfunction "2_2") (pintype "passive"))
    )
    (net (code "3") (name "/IN0") (class "Default")
      (node (ref "IC1") (pin "33") (pinfunction "RB0/AN12/INT0/LFT0/SDI/SDA_33") (pintype "bidirectional"))
      (node (ref "OK1") (pin "4") (pinfunction "COL_4") (pintype "passive"))
      (node (ref "R3") (pin "1") (pinfunction "1_1") (pintype "passive"))
    )
    (net (code "4") (name "/IN1") (class "Default")
      (node (ref "IC1") (pin "34") (pinfunction "RB1/AN10/INT1/SCK/SCL_34") (pintype "bidirectional"))
      (node (ref "OK2") (pin "4") (pinfunction "COL_4") (pintype "passive"))
      (node (ref "R5") (pin "1") (pinfunction "1_1") (pintype "passive"))
    )
    (net (code "5") (name "/IN2") (class "Default")
      (node (ref "IC1") (pin "35") (pinfunction "RB2/AN8/INT2/VMO_35") (pintype "bidirectional"))
      (node (ref "OK3") (pin "4") (pinfunction "COL_4") (pintype "passive"))
      (node (ref "R7") (pin "1") (pinfunction "1_1") (pintype "passive"))
    )
    (net (code "6") (name "/IN3") (class "Default")
      (node (ref "IC1") (pin "36") (pinfunction "RB3/AN9/CCP2/VPO_36") (pintype "bidirectional"))
      (node (ref "OK4") (pin "4") (pinfunction "COL_4") (pintype "passive"))
      (node (ref "R9") (pin "1") (pinfunction "1_1") (pintype "passive"))
    )
    (net (code "7") (name "/IN4") (class "Default")
      (node (ref "IC1") (pin "37") (pinfunction "RB4/AN11/KBI0/CSSPP_37") (pintype "bidirectional"))
      (node (ref "OK5") (pin "4") (pinfunction "COL_4") (pintype "passive"))
      (node (ref "R11") (pin "1") (pinfunction "1_1") (pintype "passive"))
    )
    (net (code "8") (name "/IN5") (class "Default")
      (node (ref "IC1") (pin "38") (pinfunction "RB5/KBI1/PGM_38") (pintype "bidirectional"))
      (node (ref "OK6") (pin "4") (pinfunction "COL_4") (pintype "passive"))
      (node (ref "R13") (pin "1") (pinfunction "1_1") (pintype "passive"))
    )
    (net (code "9") (name "/IN6") (class "Default")
      (node (ref "IC1") (pin "39") (pinfunction "RB6/KBI2/PGC_39") (pintype "bidirectional"))
      (node (ref "OK7") (pin "4") (pinfunction "COL_4") (pintype "passive"))
      (node (ref "R15") (pin "1") (pinfunction "1_1") (pintype "passive"))
    )
    (net (code "10") (name "/IN7") (class "Default")
      (node (ref "IC1") (pin "40") (pinfunction "RB7/BKI3/PGD_40") (pintype "bidirectional"))
      (node (ref "OK8") (pin "4") (pinfunction "COL_4") (pintype "passive"))
      (node (ref "R17") (pin "1") (pinfunction "1_1") (pintype "passive"))
    )
    (net (code "11") (name "/IN8") (class "Default")
      (node (ref "IC1") (pin "19") (pinfunction "RD0/SPP0_19") (pintype "bidirectional"))
      (node (ref "OK9") (pin "4") (pinfunction "COL_4") (pintype "passive"))
      (node (ref "R19") (pin "1") (pinfunction "1_1") (pintype "passive"))
    )
    (net (code "12") (name "/IN9") (class "Default")
      (node (ref "IC1") (pin "20") (pinfunction "RD1/SPP1_20") (pintype "bidirectional"))
      (node (ref "OK10") (pin "4") (pinfunction "COL_4") (pintype "passive"))
      (node (ref "R21") (pin "1") (pinfunction "1_1") (pintype "passive"))
    )
    (net (code "13") (name "/IN10") (class "Default")
      (node (ref "IC1") (pin "21") (pinfunction "RD2/SPP2_21") (pintype "bidirectional"))
      (node (ref "OK11") (pin "4") (pinfunction "COL_4") (pintype "passive"))
      (node (ref "R23") (pin "1") (pinfunction "1_1") (pintype "passive"))
    )
    (net (code "14") (name "/IN11") (class "Default")
      (node (ref "IC1") (pin "22") (pinfunction "RD3/SPP3_22") (pintype "bidirectional"))
      (node (ref "OK12") (pin "4") (pinfunction "COL_4") (pintype "passive"))
      (node (ref "R25") (pin "1") (pinfunction "1_1") (pintype "passive"))
    )
    (net (code "15") (name "/IN12") (class "Default")
      (node (ref "IC1") (pin "27") (pinfunction "RD4/SPP4_27") (pintype "bidirectional"))
      (node (ref "OK13") (pin "4") (pinfunction "COL_4") (pintype "passive"))
      (node (ref "R27") (pin "1") (pinfunction "1_1") (pintype "passive"))
    )
    (net (code "16") (name "/IN13") (class "Default")
      (node (ref "IC1") (pin "28") (pinfunction "RD5/SPP5/P1B_28") (pintype "bidirectional"))
      (node (ref "OK14") (pin "4") (pinfunction "COL_4") (pintype "passive"))
      (node (ref "R29") (pin "1") (pinfunction "1_1") (pintype "passive"))
    )
    (net (code "17") (name "/IN14") (class "Default")
      (node (ref "IC1") (pin "29") (pinfunction "RD6/SPP6/P1C_29") (pintype "bidirectional"))
      (node (ref "OK15") (pin "4") (pinfunction "COL_4") (pintype "passive"))
      (node (ref "R31") (pin "1") (pinfunction "1_1") (pintype "passive"))
    )
    (net (code "18") (name "/IN15") (class "Default")
      (node (ref "IC1") (pin "30") (pinfunction "RD7/SPP7/P1D_30") (pintype "bidirectional"))
      (node (ref "OK16") (pin "4") (pinfunction "COL_4") (pintype "passive"))
      (node (ref "R33") (pin "1") (pinfunction "1_1") (pintype "passive"))
    )
    (net (code "19") (name "/IN16") (class "Default")
      (node (ref "IC1") (pin "2") (pinfunction "RA0/AN0_2") (pintype "bidirectional"))
      (node (ref "OK17") (pin "4") (pinfunction "COL_4") (pintype "passive"))
      (node (ref "R35") (pin "1") (pinfunction "1_1") (pintype "passive"))
    )
    (net (code "20") (name "/IN17") (class "Default")
      (node (ref "IC1") (pin "3") (pinfunction "RA1/AN1_3") (pintype "bidirectional"))
      (node (ref "OK18") (pin "4") (pinfunction "COL_4") (pintype "passive"))
      (node (ref "R37") (pin "1") (pinfunction "1_1") (pintype "passive"))
    )
    (net (code "21") (name "/IN18") (class "Default")
      (node (ref "IC1") (pin "4") (pinfunction "RA2/AN2/VREF-/CVREF_4") (pintype "bidirectional"))
      (node (ref "OK19") (pin "4") (pinfunction "COL_4") (pintype "passive"))
      (node (ref "R39") (pin "1") (pinfunction "1_1") (pintype "passive"))
    )
    (net (code "22") (name "/IN19") (class "Default")
      (node (ref "IC1") (pin "5") (pinfunction "RA3/AN3/VREF+_5") (pintype "bidirectional"))
      (node (ref "OK20") (pin "4") (pinfunction "COL_4") (pintype "passive"))
      (node (ref "R41") (pin "1") (pinfunction "1_1") (pintype "passive"))
    )
    (net (code "23") (name "/OSC1") (class "Default")
      (node (ref "C4") (pin "1") (pinfunction "1_1") (pintype "passive"))
      (node (ref "IC1") (pin "13") (pinfunction "OSC1/CLKI_13") (pintype "input"))
      (node (ref "Q1") (pin "1") (pinfunction "1_1") (pintype "passive"))
    )
    (net (code "24") (name "/OSC2") (class "Default")
      (node (ref "C5") (pin "1") (pinfunction "1_1") (pintype "passive"))
      (node (ref "IC1") (pin "14") (pinfunction "RA6/OSC2/CLKO_14") (pintype "output"))
      (node (ref "Q1") (pin "2") (pinfunction "2_2") (pintype "passive"))
    )
    (net (code "25") (name "/SEN0") (class "Default")
      (node (ref "C7") (pin "-") (pinfunction "-_-") (pintype "passive"))
      (node (ref "PAD2") (pin "1") (pinfunction "P_1") (pintype "passive"))
    )
    (net (code "26") (name "/SEN1") (class "Default")
      (node (ref "C9") (pin "-") (pinfunction "-_-") (pintype "passive"))
      (node (ref "PAD3") (pin "1") (pinfunction "P_1") (pintype "passive"))
    )
    (net (code "27") (name "/SEN2") (class "Default")
      (node (ref "C11") (pin "-") (pinfunction "-_-") (pintype "passive"))
      (node (ref "PAD4") (pin "1") (pinfunction "P_1") (pintype "passive"))
    )
    (net (code "28") (name "/SEN3") (class "Default")
      (node (ref "C13") (pin "-") (pinfunction "-_-") (pintype "passive"))
      (node (ref "PAD5") (pin "1") (pinfunction "P_1") (pintype "passive"))
    )
    (net (code "29") (name "/SEN4") (class "Default")
      (node (ref "C15") (pin "-") (pinfunction "-_-") (pintype "passive"))
      (node (ref "PAD6") (pin "1") (pinfunction "P_1") (pintype "passive"))
    )
    (net (code "30") (name "/SEN5") (class "Default")
      (node (ref "C17") (pin "-") (pinfunction "-_-") (pintype "passive"))
      (node (ref "PAD7") (pin "1") (pinfunction "P_1") (pintype "passive"))
    )
    (net (code "31") (name "/SEN6") (class "Default")
      (node (ref "C19") (pin "-") (pinfunction "-_-") (pintype "passive"))
      (node (ref "PAD8") (pin "1") (pinfunction "P_1") (pintype "passive"))
    )
    (net (code "32") (name "/SEN7") (class "Default")
      (node (ref "C21") (pin "-") (pinfunction "-_-") (pintype "passive"))
      (node (ref "PAD9") (pin "1") (pinfunction "P_1") (pintype "passive"))
    )
    (net (code "33") (name "/SEN8") (class "Default")
      (node (ref "C23") (pin "-") (pinfunction "-_-") (pintype "passive"))
      (node (ref "PAD10") (pin "1") (pinfunction "P_1") (pintype "passive"))
    )
    (net (code "34") (name "/SEN9") (class "Default")
      (node (ref "C25") (pin "-") (pinfunction "-_-") (pintype "passive"))
      (node (ref "PAD11") (pin "1") (pinfunction "P_1") (pintype "passive"))
    )
    (net (code "35") (name "/SEN10") (class "Default")
      (node (ref "C27") (pin "-") (pinfunction "-_-") (pintype "passive"))
      (node (ref "PAD13") (pin "1") (pinfunction "P_1") (pintype "passive"))
    )
    (net (code "36") (name "/SEN11") (class "Default")
      (node (ref "C29") (pin "-") (pinfunction "-_-") (pintype "passive"))
      (node (ref "PAD12") (pin "1") (pinfunction "P_1") (pintype "passive"))
    )
    (net (code "37") (name "/SEN12") (class "Default")
      (node (ref "C31") (pin "-") (pinfunction "-_-") (pintype "passive"))
      (node (ref "PAD15") (pin "1") (pinfunction "P_1") (pintype "passive"))
    )
    (net (code "38") (name "/SEN13") (class "Default")
      (node (ref "C35") (pin "-") (pinfunction "-_-") (pintype "passive"))
      (node (ref "PAD14") (pin "1") (pinfunction "P_1") (pintype "passive"))
    )
    (net (code "39") (name "/SEN14") (class "Default")
      (node (ref "C33") (pin "-") (pinfunction "-_-") (pintype "passive"))
      (node (ref "PAD16") (pin "1") (pinfunction "P_1") (pintype "passive"))
    )
    (net (code "40") (name "/SEN15") (class "Default")
      (node (ref "C37") (pin "-") (pinfunction "-_-") (pintype "passive"))
      (node (ref "PAD17") (pin "1") (pinfunction "P_1") (pintype "passive"))
    )
    (net (code "41") (name "/SEN16") (class "Default")
      (node (ref "C39") (pin "-") (pinfunction "-_-") (pintype "passive"))
      (node (ref "PAD19") (pin "1") (pinfunction "P_1") (pintype "passive"))
    )
    (net (code "42") (name "/SEN17") (class "Default")
      (node (ref "C41") (pin "-") (pinfunction "-_-") (pintype "passive"))
      (node (ref "PAD18") (pin "1") (pinfunction "P_1") (pintype "passive"))
    )
    (net (code "43") (name "/SEN18") (class "Default")
      (node (ref "C43") (pin "-") (pinfunction "-_-") (pintype "passive"))
      (node (ref "PAD20") (pin "1") (pinfunction "P_1") (pintype "passive"))
    )
    (net (code "44") (name "/SEN19") (class "Default")
      (node (ref "C45") (pin "-") (pinfunction "-_-") (pintype "passive"))
      (node (ref "PAD21") (pin "1") (pinfunction "P_1") (pintype "passive"))
    )
    (net (code "45") (name "/VAL0") (class "Default")
      (node (ref "OK1") (pin "2") (pinfunction "C_2") (pintype "passive"))
      (node (ref "SW1") (pin "10") (pinfunction "10_10") (pintype "passive"))
      (node (ref "SW1") (pin "6") (pinfunction "6_6") (pintype "passive"))
      (node (ref "SW1") (pin "7") (pinfunction "7_7") (pintype "passive"))
      (node (ref "SW1") (pin "8") (pinfunction "8_8") (pintype "passive"))
      (node (ref "SW1") (pin "9") (pinfunction "9_9") (pintype "passive"))
    )
    (net (code "46") (name "/VAL1") (class "Default")
      (node (ref "OK2") (pin "2") (pinfunction "C_2") (pintype "passive"))
      (node (ref "SW2") (pin "10") (pinfunction "10_10") (pintype "passive"))
      (node (ref "SW2") (pin "6") (pinfunction "6_6") (pintype "passive"))
      (node (ref "SW2") (pin "7") (pinfunction "7_7") (pintype "passive"))
      (node (ref "SW2") (pin "8") (pinfunction "8_8") (pintype "passive"))
      (node (ref "SW2") (pin "9") (pinfunction "9_9") (pintype "passive"))
    )
    (net (code "47") (name "/VAL2") (class "Default")
      (node (ref "OK3") (pin "2") (pinfunction "C_2") (pintype "passive"))
      (node (ref "SW3") (pin "10") (pinfunction "10_10") (pintype "passive"))
      (node (ref "SW3") (pin "6") (pinfunction "6_6") (pintype "passive"))
      (node (ref "SW3") (pin "7") (pinfunction "7_7") (pintype "passive"))
      (node (ref "SW3") (pin "8") (pinfunction "8_8") (pintype "passive"))
      (node (ref "SW3") (pin "9") (pinfunction "9_9") (pintype "passive"))
    )
    (net (code "48") (name "/VAL3") (class "Default")
      (node (ref "OK4") (pin "2") (pinfunction "C_2") (pintype "passive"))
      (node (ref "SW4") (pin "10") (pinfunction "10_10") (pintype "passive"))
      (node (ref "SW4") (pin "6") (pinfunction "6_6") (pintype "passive"))
      (node (ref "SW4") (pin "7") (pinfunction "7_7") (pintype "passive"))
      (node (ref "SW4") (pin "8") (pinfunction "8_8") (pintype "passive"))
      (node (ref "SW4") (pin "9") (pinfunction "9_9") (pintype "passive"))
    )
    (net (code "49") (name "/VAL4") (class "Default")
      (node (ref "OK5") (pin "2") (pinfunction "C_2") (pintype "passive"))
      (node (ref "SW5") (pin "10") (pinfunction "10_10") (pintype "passive"))
      (node (ref "SW5") (pin "6") (pinfunction "6_6") (pintype "passive"))
      (node (ref "SW5") (pin "7") (pinfunction "7_7") (pintype "passive"))
      (node (ref "SW5") (pin "8") (pinfunction "8_8") (pintype "passive"))
      (node (ref "SW5") (pin "9") (pinfunction "9_9") (pintype "passive"))
    )
    (net (code "50") (name "/VAL5") (class "Default")
      (node (ref "OK6") (pin "2") (pinfunction "C_2") (pintype "passive"))
      (node (ref "SW6") (pin "10") (pinfunction "10_10") (pintype "passive"))
      (node (ref "SW6") (pin "6") (pinfunction "6_6") (pintype "passive"))
      (node (ref "SW6") (pin "7") (pinfunction "7_7") (pintype "passive"))
      (node (ref "SW6") (pin "8") (pinfunction "8_8") (pintype "passive"))
      (node (ref "SW6") (pin "9") (pinfunction "9_9") (pintype "passive"))
    )
    (net (code "51") (name "/VAL6") (class "Default")
      (node (ref "OK7") (pin "2") (pinfunction "C_2") (pintype "passive"))
      (node (ref "SW7") (pin "10") (pinfunction "10_10") (pintype "passive"))
      (node (ref "SW7") (pin "6") (pinfunction "6_6") (pintype "passive"))
      (node (ref "SW7") (pin "7") (pinfunction "7_7") (pintype "passive"))
      (node (ref "SW7") (pin "8") (pinfunction "8_8") (pintype "passive"))
      (node (ref "SW7") (pin "9") (pinfunction "9_9") (pintype "passive"))
    )
    (net (code "52") (name "/VAL7") (class "Default")
      (node (ref "OK8") (pin "2") (pinfunction "C_2") (pintype "passive"))
      (node (ref "SW8") (pin "10") (pinfunction "10_10") (pintype "passive"))
      (node (ref "SW8") (pin "6") (pinfunction "6_6") (pintype "passive"))
      (node (ref "SW8") (pin "7") (pinfunction "7_7") (pintype "passive"))
      (node (ref "SW8") (pin "8") (pinfunction "8_8") (pintype "passive"))
      (node (ref "SW8") (pin "9") (pinfunction "9_9") (pintype "passive"))
    )
    (net (code "53") (name "/VAL8") (class "Default")
      (node (ref "OK9") (pin "2") (pinfunction "C_2") (pintype "passive"))
      (node (ref "SW9") (pin "10") (pinfunction "10_10") (pintype "passive"))
      (node (ref "SW9") (pin "6") (pinfunction "6_6") (pintype "passive"))
      (node (ref "SW9") (pin "7") (pinfunction "7_7") (pintype "passive"))
      (node (ref "SW9") (pin "8") (pinfunction "8_8") (pintype "passive"))
      (node (ref "SW9") (pin "9") (pinfunction "9_9") (pintype "passive"))
    )
    (net (code "54") (name "/VAL9") (class "Default")
      (node (ref "OK10") (pin "2") (pinfunction "C_2") (pintype "passive"))
      (node (ref "SW10") (pin "10") (pinfunction "10_10") (pintype "passive"))
      (node (ref "SW10") (pin "6") (pinfunction "6_6") (pintype "passive"))
      (node (ref "SW10") (pin "7") (pinfunction "7_7") (pintype "passive"))
      (node (ref "SW10") (pin "8") (pinfunction "8_8") (pintype "passive"))
      (node (ref "SW10") (pin "9") (pinfunction "9_9") (pintype "passive"))
    )
    (net (code "55") (name "/VAL10") (class "Default")
      (node (ref "OK11") (pin "2") (pinfunction "C_2") (pintype "passive"))
      (node (ref "SW11") (pin "10") (pinfunction "10_10") (pintype "passive"))
      (node (ref "SW11") (pin "6") (pinfunction "6_6") (pintype "passive"))
      (node (ref "SW11") (pin "7") (pinfunction "7_7") (pintype "passive"))
      (node (ref "SW11") (pin "8") (pinfunction "8_8") (pintype "passive"))
      (node (ref "SW11") (pin "9") (pinfunction "9_9") (pintype "passive"))
    )
    (net (code "56") (name "/VAL11") (class "Default")
      (node (ref "OK12") (pin "2") (pinfunction "C_2") (pintype "passive"))
      (node (ref "SW12") (pin "10") (pinfunction "10_10") (pintype "passive"))
      (node (ref "SW12") (pin "6") (pinfunction "6_6") (pintype "passive"))
      (node (ref "SW12") (pin "7") (pinfunction "7_7") (pintype "passive"))
      (node (ref "SW12") (pin "8") (pinfunction "8_8") (pintype "passive"))
      (node (ref "SW12") (pin "9") (pinfunction "9_9") (pintype "passive"))
    )
    (net (code "57") (name "/VAL12") (class "Default")
      (node (ref "OK13") (pin "2") (pinfunction "C_2") (pintype "passive"))
      (node (ref "SW13") (pin "10") (pinfunction "10_10") (pintype "passive"))
      (node (ref "SW13") (pin "6") (pinfunction "6_6") (pintype "passive"))
      (node (ref "SW13") (pin "7") (pinfunction "7_7") (pintype "passive"))
      (node (ref "SW13") (pin "8") (pinfunction "8_8") (pintype "passive"))
      (node (ref "SW13") (pin "9") (pinfunction "9_9") (pintype "passive"))
    )
    (net (code "58") (name "/VAL13") (class "Default")
      (node (ref "OK14") (pin "2") (pinfunction "C_2") (pintype "passive"))
      (node (ref "SW15") (pin "10") (pinfunction "10_10") (pintype "passive"))
      (node (ref "SW15") (pin "6") (pinfunction "6_6") (pintype "passive"))
      (node (ref "SW15") (pin "7") (pinfunction "7_7") (pintype "passive"))
      (node (ref "SW15") (pin "8") (pinfunction "8_8") (pintype "passive"))
      (node (ref "SW15") (pin "9") (pinfunction "9_9") (pintype "passive"))
    )
    (net (code "59") (name "/VAL14") (class "Default")
      (node (ref "OK15") (pin "2") (pinfunction "C_2") (pintype "passive"))
      (node (ref "SW14") (pin "10") (pinfunction "10_10") (pintype "passive"))
      (node (ref "SW14") (pin "6") (pinfunction "6_6") (pintype "passive"))
      (node (ref "SW14") (pin "7") (pinfunction "7_7") (pintype "passive"))
      (node (ref "SW14") (pin "8") (pinfunction "8_8") (pintype "passive"))
      (node (ref "SW14") (pin "9") (pinfunction "9_9") (pintype "passive"))
    )
    (net (code "60") (name "/VAL15") (class "Default")
      (node (ref "OK16") (pin "2") (pinfunction "C_2") (pintype "passive"))
      (node (ref "SW16") (pin "10") (pinfunction "10_10") (pintype "passive"))
      (node (ref "SW16") (pin "6") (pinfunction "6_6") (pintype "passive"))
      (node (ref "SW16") (pin "7") (pinfunction "7_7") (pintype "passive"))
      (node (ref "SW16") (pin "8") (pinfunction "8_8") (pintype "passive"))
      (node (ref "SW16") (pin "9") (pinfunction "9_9") (pintype "passive"))
    )
    (net (code "61") (name "/VAL16") (class "Default")
      (node (ref "OK17") (pin "2") (pinfunction "C_2") (pintype "passive"))
      (node (ref "SW17") (pin "10") (pinfunction "10_10") (pintype "passive"))
      (node (ref "SW17") (pin "6") (pinfunction "6_6") (pintype "passive"))
      (node (ref "SW17") (pin "7") (pinfunction "7_7") (pintype "passive"))
      (node (ref "SW17") (pin "8") (pinfunction "8_8") (pintype "passive"))
      (node (ref "SW17") (pin "9") (pinfunction "9_9") (pintype "passive"))
    )
    (net (code "62") (name "/VAL17") (class "Default")
      (node (ref "OK18") (pin "2") (pinfunction "C_2") (pintype "passive"))
      (node (ref "SW18") (pin "10") (pinfunction "10_10") (pintype "passive"))
      (node (ref "SW18") (pin "6") (pinfunction "6_6") (pintype "passive"))
      (node (ref "SW18") (pin "7") (pinfunction "7_7") (pintype "passive"))
      (node (ref "SW18") (pin "8") (pinfunction "8_8") (pintype "passive"))
      (node (ref "SW18") (pin "9") (pinfunction "9_9") (pintype "passive"))
    )
    (net (code "63") (name "/VAL18") (class "Default")
      (node (ref "OK19") (pin "2") (pinfunction "C_2") (pintype "passive"))
      (node (ref "SW19") (pin "10") (pinfunction "10_10") (pintype "passive"))
      (node (ref "SW19") (pin "6") (pinfunction "6_6") (pintype "passive"))
      (node (ref "SW19") (pin "7") (pinfunction "7_7") (pintype "passive"))
      (node (ref "SW19") (pin "8") (pinfunction "8_8") (pintype "passive"))
      (node (ref "SW19") (pin "9") (pinfunction "9_9") (pintype "passive"))
    )
    (net (code "64") (name "/VAL19") (class "Default")
      (node (ref "OK20") (pin "2") (pinfunction "C_2") (pintype "passive"))
      (node (ref "SW20") (pin "10") (pinfunction "10_10") (pintype "passive"))
      (node (ref "SW20") (pin "6") (pinfunction "6_6") (pintype "passive"))
      (node (ref "SW20") (pin "7") (pinfunction "7_7") (pintype "passive"))
      (node (ref "SW20") (pin "8") (pinfunction "8_8") (pintype "passive"))
      (node (ref "SW20") (pin "9") (pinfunction "9_9") (pintype "passive"))
    )
    (net (code "65") (name "DGND") (class "Default")
      (node (ref "C1") (pin "2") (pinfunction "2_2") (pintype "passive"))
      (node (ref "C2") (pin "2") (pinfunction "2_2") (pintype "passive"))
      (node (ref "C3") (pin "2") (pinfunction "2_2") (pintype "passive"))
      (node (ref "C4") (pin "2") (pinfunction "2_2") (pintype "passive"))
      (node (ref "C5") (pin "2") (pinfunction "2_2") (pintype "passive"))
      (node (ref "IC1") (pin "12") (pinfunction "VSS_12") (pintype "power_in"))
      (node (ref "IC1") (pin "31") (pinfunction "VSS_31") (pintype "power_in"))
      (node (ref "IC1") (pin "6") (pinfunction "RA4/T0CKI/CIOUT/RCV_6") (pintype "bidirectional"))
      (node (ref "IC1") (pin "7") (pinfunction "RA5/AN4/~{SS}/HLVDIN/C2OUT_7") (pintype "bidirectional"))
      (node (ref "OK1") (pin "3") (pinfunction "EMIT_3") (pintype "passive"))
      (node (ref "OK10") (pin "3") (pinfunction "EMIT_3") (pintype "passive"))
      (node (ref "OK11") (pin "3") (pinfunction "EMIT_3") (pintype "passive"))
      (node (ref "OK12") (pin "3") (pinfunction "EMIT_3") (pintype "passive"))
      (node (ref "OK13") (pin "3") (pinfunction "EMIT_3") (pintype "passive"))
      (node (ref "OK14") (pin "3") (pinfunction "EMIT_3") (pintype "passive"))
      (node (ref "OK15") (pin "3") (pinfunction "EMIT_3") (pintype "passive"))
      (node (ref "OK16") (pin "3") (pinfunction "EMIT_3") (pintype "passive"))
      (node (ref "OK17") (pin "3") (pinfunction "EMIT_3") (pintype "passive"))
      (node (ref "OK18") (pin "3") (pinfunction "EMIT_3") (pintype "passive"))
      (node (ref "OK19") (pin "3") (pinfunction "EMIT_3") (pintype "passive"))
      (node (ref "OK2") (pin "3") (pinfunction "EMIT_3") (pintype "passive"))
      (node (ref "OK20") (pin "3") (pinfunction "EMIT_3") (pintype "passive"))
      (node (ref "OK3") (pin "3") (pinfunction "EMIT_3") (pintype "passive"))
      (node (ref "OK4") (pin "3") (pinfunction "EMIT_3") (pintype "passive"))
      (node (ref "OK5") (pin "3") (pinfunction "EMIT_3") (pintype "passive"))
      (node (ref "OK6") (pin "3") (pinfunction "EMIT_3") (pintype "passive"))
      (node (ref "OK7") (pin "3") (pinfunction "EMIT_3") (pintype "passive"))
      (node (ref "OK8") (pin "3") (pinfunction "EMIT_3") (pintype "passive"))
      (node (ref "OK9") (pin "3") (pinfunction "EMIT_3") (pintype "passive"))
      (node (ref "X1") (pin "4") (pinfunction "4_4") (pintype "passive"))
      (node (ref "X1") (pin "S1") (pinfunction "S1_S1") (pintype "passive"))
      (node (ref "X1") (pin "S2") (pinfunction "S2_S2") (pintype "passive"))
    )
    (net (code "66") (name "GND") (class "Default")
      (node (ref "C10") (pin "-") (pinfunction "-_-") (pintype "passive"))
      (node (ref "C12") (pin "-") (pinfunction "-_-") (pintype "passive"))
      (node (ref "C14") (pin "-") (pinfunction "-_-") (pintype "passive"))
      (node (ref "C16") (pin "-") (pinfunction "-_-") (pintype "passive"))
      (node (ref "C18") (pin "-") (pinfunction "-_-") (pintype "passive"))
      (node (ref "C20") (pin "-") (pinfunction "-_-") (pintype "passive"))
      (node (ref "C22") (pin "-") (pinfunction "-_-") (pintype "passive"))
      (node (ref "C24") (pin "-") (pinfunction "-_-") (pintype "passive"))
      (node (ref "C26") (pin "-") (pinfunction "-_-") (pintype "passive"))
      (node (ref "C28") (pin "-") (pinfunction "-_-") (pintype "passive"))
      (node (ref "C30") (pin "-") (pinfunction "-_-") (pintype "passive"))
      (node (ref "C32") (pin "-") (pinfunction "-_-") (pintype "passive"))
      (node (ref "C34") (pin "-") (pinfunction "-_-") (pintype "passive"))
      (node (ref "C36") (pin "-") (pinfunction "-_-") (pintype "passive"))
      (node (ref "C38") (pin "-") (pinfunction "-_-") (pintype "passive"))
      (node (ref "C40") (pin "-") (pinfunction "-_-") (pintype "passive"))
      (node (ref "C42") (pin "-") (pinfunction "-_-") (pintype "passive"))
      (node (ref "C44") (pin "-") (pinfunction "-_-") (pintype "passive"))
      (node (ref "C48") (pin "2") (pinfunction "2_2") (pintype "passive"))
      (node (ref "C6") (pin "-") (pinfunction "-_-") (pintype "passive"))
      (node (ref "C8") (pin "-") (pinfunction "-_-") (pintype "passive"))
      (node (ref "IC10") (pin "5") (pinfunction "GND_5") (pintype "input"))
      (node (ref "IC11") (pin "5") (pinfunction "GND_5") (pintype "input"))
      (node (ref "IC12") (pin "5") (pinfunction "GND_5") (pintype "input"))
      (node (ref "IC13") (pin "5") (pinfunction "GND_5") (pintype "input"))
      (node (ref "IC14") (pin "5") (pinfunction "GND_5") (pintype "input"))
      (node (ref "IC15") (pin "5") (pinfunction "GND_5") (pintype "input"))
      (node (ref "IC16") (pin "5") (pinfunction "GND_5") (pintype "input"))
      (node (ref "IC17") (pin "5") (pinfunction "GND_5") (pintype "input"))
      (node (ref "IC18") (pin "5") (pinfunction "GND_5") (pintype "input"))
      (node (ref "IC19") (pin "5") (pinfunction "GND_5") (pintype "input"))
      (node (ref "IC2") (pin "5") (pinfunction "GND_5") (pintype "input"))
      (node (ref "IC20") (pin "5") (pinfunction "GND_5") (pintype "input"))
      (node (ref "IC21") (pin "5") (pinfunction "GND_5") (pintype "input"))
      (node (ref "IC3") (pin "5") (pinfunction "GND_5") (pintype "input"))
      (node (ref "IC4") (pin "5") (pinfunction "GND_5") (pintype "input"))
      (node (ref "IC5") (pin "5") (pinfunction "GND_5") (pintype "input"))
      (node (ref "IC6") (pin "5") (pinfunction "GND_5") (pintype "input"))
      (node (ref "IC7") (pin "5") (pinfunction "GND_5") (pintype "input"))
      (node (ref "IC8") (pin "5") (pinfunction "GND_5") (pintype "input"))
      (node (ref "IC9") (pin "5") (pinfunction "GND_5") (pintype "input"))
      (node (ref "J2") (pin "1A") (pinfunction "1_1A") (pintype "passive"))
      (node (ref "J2") (pin "1B") (pinfunction "1_1B") (pintype "passive"))
      (node (ref "J3") (pin "1A") (pinfunction "1_1A") (pintype "passive"))
      (node (ref "J3") (pin "1B") (pinfunction "1_1B") (pintype "passive"))
      (node (ref "LED1") (pin "K") (pinfunction "C_K") (pintype "passive"))
      (node (ref "R42") (pin "1") (pinfunction "1_1") (pintype "passive"))
      (node (ref "R43") (pin "E") (pinfunction "E_E") (pintype "passive"))
      (node (ref "R44") (pin "1") (pinfunction "1_1") (pintype "passive"))
      (node (ref "R45") (pin "E") (pinfunction "E_E") (pintype "passive"))
      (node (ref "R46") (pin "1") (pinfunction "1_1") (pintype "passive"))
      (node (ref "R47") (pin "E") (pinfunction "E_E") (pintype "passive"))
      (node (ref "R48") (pin "1") (pinfunction "1_1") (pintype "passive"))
      (node (ref "R49") (pin "E") (pinfunction "E_E") (pintype "passive"))
      (node (ref "R50") (pin "1") (pinfunction "1_1") (pintype "passive"))
      (node (ref "R51") (pin "E") (pinfunction "E_E") (pintype "passive"))
      (node (ref "R52") (pin "1") (pinfunction "1_1") (pintype "passive"))
      (node (ref "R53") (pin "E") (pinfunction "E_E") (pintype "passive"))
      (node (ref "R54") (pin "1") (pinfunction "1_1") (pintype "passive"))
      (node (ref "R55") (pin "E") (pinfunction "E_E") (pintype "passive"))
      (node (ref "R56") (pin "1") (pinfunction "1_1") (pintype "passive"))
      (node (ref "R57") (pin "E") (pinfunction "E_E") (pintype "passive"))
      (node (ref "R58") (pin "1") (pinfunction "1_1") (pintype "passive"))
      (node (ref "R59") (pin "E") (pinfunction "E_E") (pintype "passive"))
      (node (ref "R60") (pin "1") (pinfunction "1_1") (pintype "passive"))
      (node (ref "R61") (pin "E") (pinfunction "E_E") (pintype "passive"))
      (node (ref "R62") (pin "1") (pinfunction "1_1") (pintype "passive"))
      (node (ref "R63") (pin "E") (pinfunction "E_E") (pintype "passive"))
      (node (ref "R64") (pin "1") (pinfunction "1_1") (pintype "passive"))
      (node (ref "R65") (pin "E") (pinfunction "E_E") (pintype "passive"))
      (node (ref "R66") (pin "1") (pinfunction "1_1") (pintype "passive"))
      (node (ref "R67") (pin "E") (pinfunction "E_E") (pintype "passive"))
      (node (ref "R68") (pin "1") (pinfunction "1_1") (pintype "passive"))
      (node (ref "R69") (pin "E") (pinfunction "E_E") (pintype "passive"))
      (node (ref "R70") (pin "1") (pinfunction "1_1") (pintype "passive"))
      (node (ref "R71") (pin "E") (pinfunction "E_E") (pintype "passive"))
      (node (ref "R72") (pin "1") (pinfunction "1_1") (pintype "passive"))
      (node (ref "R73") (pin "E") (pinfunction "E_E") (pintype "passive"))
      (node (ref "R74") (pin "1") (pinfunction "1_1") (pintype "passive"))
      (node (ref "R75") (pin "E") (pinfunction "E_E") (pintype "passive"))
      (node (ref "R76") (pin "1") (pinfunction "1_1") (pintype "passive"))
      (node (ref "R77") (pin "E") (pinfunction "E_E") (pintype "passive"))
      (node (ref "R78") (pin "1") (pinfunction "1_1") (pintype "passive"))
      (node (ref "R79") (pin "E") (pinfunction "E_E") (pintype "passive"))
      (node (ref "R80") (pin "1") (pinfunction "1_1") (pintype "passive"))
      (node (ref "R81") (pin "E") (pinfunction "E_E") (pintype "passive"))
      (node (ref "R82") (pin "1") (pinfunction "1_1") (pintype "passive"))
    )
    (net (code "67") (name "Net-(D1-PadA)") (class "Default")
      (node (ref "D1") (pin "A") (pinfunction "A_A") (pintype "passive"))
      (node (ref "J1") (pin "3") (pinfunction "3_3") (pintype "passive"))
    )
    (net (code "68") (name "Net-(IC1-RC4{slash}D-{slash}VM)") (class "Default")
      (node (ref "IC1") (pin "23") (pinfunction "RC4/D-/VM_23") (pintype "bidirectional"))
      (node (ref "X1") (pin "2") (pinfunction "2_2") (pintype "passive"))
    )
    (net (code "69") (name "Net-(IC1-RC5{slash}D+{slash}VP)") (class "Default")
      (node (ref "IC1") (pin "24") (pinfunction "RC5/D+/VP_24") (pintype "bidirectional"))
      (node (ref "X1") (pin "3") (pinfunction "3_3") (pintype "passive"))
    )
    (net (code "70") (name "Net-(IC1-VUSB)") (class "Default")
      (node (ref "C1") (pin "1") (pinfunction "1_1") (pintype "passive"))
      (node (ref "IC1") (pin "18") (pinfunction "VUSB_18") (pintype "bidirectional"))
    )
    (net (code "71") (name "Net-(IC1-~{MCLR}{slash}VPP{slash}RE3)") (class "Default")
      (node (ref "IC1") (pin "1") (pinfunction "~{MCLR}/VPP/RE3_1") (pintype "input"))
      (node (ref "R1") (pin "1") (pinfunction "1_1") (pintype "passive"))
    )
    (net (code "72") (name "Net-(IC2-D1)") (class "Default")
      (node (ref "IC2") (pin "1") (pinfunction "D1_1") (pintype "output"))
      (node (ref "SW1") (pin "1") (pinfunction "1_1") (pintype "passive"))
    )
    (net (code "73") (name "Net-(IC2-D2)") (class "Default")
      (node (ref "IC2") (pin "2") (pinfunction "D2_2") (pintype "output"))
      (node (ref "SW1") (pin "2") (pinfunction "2_2") (pintype "passive"))
    )
    (net (code "74") (name "Net-(IC2-D3)") (class "Default")
      (node (ref "IC2") (pin "3") (pinfunction "D3_3") (pintype "output"))
      (node (ref "SW1") (pin "3") (pinfunction "3_3") (pintype "passive"))
    )
    (net (code "75") (name "Net-(IC2-D4)") (class "Default")
      (node (ref "IC2") (pin "4") (pinfunction "D4_4") (pintype "output"))
      (node (ref "SW1") (pin "4") (pinfunction "4_4") (pintype "passive"))
    )
    (net (code "76") (name "Net-(IC2-D5)") (class "Default")
      (node (ref "IC2") (pin "6") (pinfunction "D5_6") (pintype "input"))
      (node (ref "SW1") (pin "5") (pinfunction "5_5") (pintype "passive"))
    )
    (net (code "77") (name "Net-(IC2-IN)") (class "Default")
      (node (ref "C7") (pin "+") (pinfunction "+_+") (pintype "passive"))
      (node (ref "IC2") (pin "8") (pinfunction "IN_8") (pintype "input"))
      (node (ref "R43") (pin "A") (pinfunction "A_A") (pintype "passive"))
      (node (ref "R43") (pin "S") (pinfunction "S_S") (pintype "passive"))
    )
    (net (code "78") (name "Net-(IC2-OUT)") (class "Default")
      (node (ref "C6") (pin "+") (pinfunction "+_+") (pintype "passive"))
      (node (ref "IC2") (pin "7") (pinfunction "OUT_7") (pintype "input"))
      (node (ref "R42") (pin "2") (pinfunction "2_2") (pintype "passive"))
    )
    (net (code "79") (name "Net-(IC3-D1)") (class "Default")
      (node (ref "IC3") (pin "1") (pinfunction "D1_1") (pintype "output"))
      (node (ref "SW2") (pin "1") (pinfunction "1_1") (pintype "passive"))
    )
    (net (code "80") (name "Net-(IC3-D2)") (class "Default")
      (node (ref "IC3") (pin "2") (pinfunction "D2_2") (pintype "output"))
      (node (ref "SW2") (pin "2") (pinfunction "2_2") (pintype "passive"))
    )
    (net (code "81") (name "Net-(IC3-D3)") (class "Default")
      (node (ref "IC3") (pin "3") (pinfunction "D3_3") (pintype "output"))
      (node (ref "SW2") (pin "3") (pinfunction "3_3") (pintype "passive"))
    )
    (net (code "82") (name "Net-(IC3-D4)") (class "Default")
      (node (ref "IC3") (pin "4") (pinfunction "D4_4") (pintype "output"))
      (node (ref "SW2") (pin "4") (pinfunction "4_4") (pintype "passive"))
    )
    (net (code "83") (name "Net-(IC3-D5)") (class "Default")
      (node (ref "IC3") (pin "6") (pinfunction "D5_6") (pintype "input"))
      (node (ref "SW2") (pin "5") (pinfunction "5_5") (pintype "passive"))
    )
    (net (code "84") (name "Net-(IC3-IN)") (class "Default")
      (node (ref "C9") (pin "+") (pinfunction "+_+") (pintype "passive"))
      (node (ref "IC3") (pin "8") (pinfunction "IN_8") (pintype "input"))
      (node (ref "R45") (pin "A") (pinfunction "A_A") (pintype "passive"))
      (node (ref "R45") (pin "S") (pinfunction "S_S") (pintype "passive"))
    )
    (net (code "85") (name "Net-(IC3-OUT)") (class "Default")
      (node (ref "C8") (pin "+") (pinfunction "+_+") (pintype "passive"))
      (node (ref "IC3") (pin "7") (pinfunction "OUT_7") (pintype "input"))
      (node (ref "R44") (pin "2") (pinfunction "2_2") (pintype "passive"))
    )
    (net (code "86") (name "Net-(IC4-D1)") (class "Default")
      (node (ref "IC4") (pin "1") (pinfunction "D1_1") (pintype "output"))
      (node (ref "SW3") (pin "1") (pinfunction "1_1") (pintype "passive"))
    )
    (net (code "87") (name "Net-(IC4-D2)") (class "Default")
      (node (ref "IC4") (pin "2") (pinfunction "D2_2") (pintype "output"))
      (node (ref "SW3") (pin "2") (pinfunction "2_2") (pintype "passive"))
    )
    (net (code "88") (name "Net-(IC4-D3)") (class "Default")
      (node (ref "IC4") (pin "3") (pinfunction "D3_3") (pintype "output"))
      (node (ref "SW3") (pin "3") (pinfunction "3_3") (pintype "passive"))
    )
    (net (code "89") (name "Net-(IC4-D4)") (class "Default")
      (node (ref "IC4") (pin "4") (pinfunction "D4_4") (pintype "output"))
      (node (ref "SW3") (pin "4") (pinfunction "4_4") (pintype "passive"))
    )
    (net (code "90") (name "Net-(IC4-D5)") (class "Default")
      (node (ref "IC4") (pin "6") (pinfunction "D5_6") (pintype "input"))
      (node (ref "SW3") (pin "5") (pinfunction "5_5") (pintype "passive"))
    )
    (net (code "91") (name "Net-(IC4-IN)") (class "Default")
      (node (ref "C11") (pin "+") (pinfunction "+_+") (pintype "passive"))
      (node (ref "IC4") (pin "8") (pinfunction "IN_8") (pintype "input"))
      (node (ref "R47") (pin "A") (pinfunction "A_A") (pintype "passive"))
      (node (ref "R47") (pin "S") (pinfunction "S_S") (pintype "passive"))
    )
    (net (code "92") (name "Net-(IC4-OUT)") (class "Default")
      (node (ref "C10") (pin "+") (pinfunction "+_+") (pintype "passive"))
      (node (ref "IC4") (pin "7") (pinfunction "OUT_7") (pintype "input"))
      (node (ref "R46") (pin "2") (pinfunction "2_2") (pintype "passive"))
    )
    (net (code "93") (name "Net-(IC5-D1)") (class "Default")
      (node (ref "IC5") (pin "1") (pinfunction "D1_1") (pintype "output"))
      (node (ref "SW4") (pin "1") (pinfunction "1_1") (pintype "passive"))
    )
    (net (code "94") (name "Net-(IC5-D2)") (class "Default")
      (node (ref "IC5") (pin "2") (pinfunction "D2_2") (pintype "output"))
      (node (ref "SW4") (pin "2") (pinfunction "2_2") (pintype "passive"))
    )
    (net (code "95") (name "Net-(IC5-D3)") (class "Default")
      (node (ref "IC5") (pin "3") (pinfunction "D3_3") (pintype "output"))
      (node (ref "SW4") (pin "3") (pinfunction "3_3") (pintype "passive"))
    )
    (net (code "96") (name "Net-(IC5-D4)") (class "Default")
      (node (ref "IC5") (pin "4") (pinfunction "D4_4") (pintype "output"))
      (node (ref "SW4") (pin "4") (pinfunction "4_4") (pintype "passive"))
    )
    (net (code "97") (name "Net-(IC5-D5)") (class "Default")
      (node (ref "IC5") (pin "6") (pinfunction "D5_6") (pintype "input"))
      (node (ref "SW4") (pin "5") (pinfunction "5_5") (pintype "passive"))
    )
    (net (code "98") (name "Net-(IC5-IN)") (class "Default")
      (node (ref "C13") (pin "+") (pinfunction "+_+") (pintype "passive"))
      (node (ref "IC5") (pin "8") (pinfunction "IN_8") (pintype "input"))
      (node (ref "R49") (pin "A") (pinfunction "A_A") (pintype "passive"))
      (node (ref "R49") (pin "S") (pinfunction "S_S") (pintype "passive"))
    )
    (net (code "99") (name "Net-(IC5-OUT)") (class "Default")
      (node (ref "C12") (pin "+") (pinfunction "+_+") (pintype "passive"))
      (node (ref "IC5") (pin "7") (pinfunction "OUT_7") (pintype "input"))
      (node (ref "R48") (pin "2") (pinfunction "2_2") (pintype "passive"))
    )
    (net (code "100") (name "Net-(IC6-D1)") (class "Default")
      (node (ref "IC6") (pin "1") (pinfunction "D1_1") (pintype "output"))
      (node (ref "SW5") (pin "1") (pinfunction "1_1") (pintype "passive"))
    )
    (net (code "101") (name "Net-(IC6-D2)") (class "Default")
      (node (ref "IC6") (pin "2") (pinfunction "D2_2") (pintype "output"))
      (node (ref "SW5") (pin "2") (pinfunction "2_2") (pintype "passive"))
    )
    (net (code "102") (name "Net-(IC6-D3)") (class "Default")
      (node (ref "IC6") (pin "3") (pinfunction "D3_3") (pintype "output"))
      (node (ref "SW5") (pin "3") (pinfunction "3_3") (pintype "passive"))
    )
    (net (code "103") (name "Net-(IC6-D4)") (class "Default")
      (node (ref "IC6") (pin "4") (pinfunction "D4_4") (pintype "output"))
      (node (ref "SW5") (pin "4") (pinfunction "4_4") (pintype "passive"))
    )
    (net (code "104") (name "Net-(IC6-D5)") (class "Default")
      (node (ref "IC6") (pin "6") (pinfunction "D5_6") (pintype "input"))
      (node (ref "SW5") (pin "5") (pinfunction "5_5") (pintype "passive"))
    )
    (net (code "105") (name "Net-(IC6-IN)") (class "Default")
      (node (ref "C15") (pin "+") (pinfunction "+_+") (pintype "passive"))
      (node (ref "IC6") (pin "8") (pinfunction "IN_8") (pintype "input"))
      (node (ref "R51") (pin "A") (pinfunction "A_A") (pintype "passive"))
      (node (ref "R51") (pin "S") (pinfunction "S_S") (pintype "passive"))
    )
    (net (code "106") (name "Net-(IC6-OUT)") (class "Default")
      (node (ref "C14") (pin "+") (pinfunction "+_+") (pintype "passive"))
      (node (ref "IC6") (pin "7") (pinfunction "OUT_7") (pintype "input"))
      (node (ref "R50") (pin "2") (pinfunction "2_2") (pintype "passive"))
    )
    (net (code "107") (name "Net-(IC7-D1)") (class "Default")
      (node (ref "IC7") (pin "1") (pinfunction "D1_1") (pintype "output"))
      (node (ref "SW6") (pin "1") (pinfunction "1_1") (pintype "passive"))
    )
    (net (code "108") (name "Net-(IC7-D2)") (class "Default")
      (node (ref "IC7") (pin "2") (pinfunction "D2_2") (pintype "output"))
      (node (ref "SW6") (pin "2") (pinfunction "2_2") (pintype "passive"))
    )
    (net (code "109") (name "Net-(IC7-D3)") (class "Default")
      (node (ref "IC7") (pin "3") (pinfunction "D3_3") (pintype "output"))
      (node (ref "SW6") (pin "3") (pinfunction "3_3") (pintype "passive"))
    )
    (net (code "110") (name "Net-(IC7-D4)") (class "Default")
      (node (ref "IC7") (pin "4") (pinfunction "D4_4") (pintype "output"))
      (node (ref "SW6") (pin "4") (pinfunction "4_4") (pintype "passive"))
    )
    (net (code "111") (name "Net-(IC7-D5)") (class "Default")
      (node (ref "IC7") (pin "6") (pinfunction "D5_6") (pintype "input"))
      (node (ref "SW6") (pin "5") (pinfunction "5_5") (pintype "passive"))
    )
    (net (code "112") (name "Net-(IC7-IN)") (class "Default")
      (node (ref "C17") (pin "+") (pinfunction "+_+") (pintype "passive"))
      (node (ref "IC7") (pin "8") (pinfunction "IN_8") (pintype "input"))
      (node (ref "R53") (pin "A") (pinfunction "A_A") (pintype "passive"))
      (node (ref "R53") (pin "S") (pinfunction "S_S") (pintype "passive"))
    )
    (net (code "113") (name "Net-(IC7-OUT)") (class "Default")
      (node (ref "C16") (pin "+") (pinfunction "+_+") (pintype "passive"))
      (node (ref "IC7") (pin "7") (pinfunction "OUT_7") (pintype "input"))
      (node (ref "R52") (pin "2") (pinfunction "2_2") (pintype "passive"))
    )
    (net (code "114") (name "Net-(IC8-D1)") (class "Default")
      (node (ref "IC8") (pin "1") (pinfunction "D1_1") (pintype "output"))
      (node (ref "SW7") (pin "1") (pinfunction "1_1") (pintype "passive"))
    )
    (net (code "115") (name "Net-(IC8-D2)") (class "Default")
      (node (ref "IC8") (pin "2") (pinfunction "D2_2") (pintype "output"))
      (node (ref "SW7") (pin "2") (pinfunction "2_2") (pintype "passive"))
    )
    (net (code "116") (name "Net-(IC8-D3)") (class "Default")
      (node (ref "IC8") (pin "3") (pinfunction "D3_3") (pintype "output"))
      (node (ref "SW7") (pin "3") (pinfunction "3_3") (pintype "passive"))
    )
    (net (code "117") (name "Net-(IC8-D4)") (class "Default")
      (node (ref "IC8") (pin "4") (pinfunction "D4_4") (pintype "output"))
      (node (ref "SW7") (pin "4") (pinfunction "4_4") (pintype "passive"))
    )
    (net (code "118") (name "Net-(IC8-D5)") (class "Default")
      (node (ref "IC8") (pin "6") (pinfunction "D5_6") (pintype "input"))
      (node (ref "SW7") (pin "5") (pinfunction "5_5") (pintype "passive"))
    )
    (net (code "119") (name "Net-(IC8-IN)") (class "Default")
      (node (ref "C19") (pin "+") (pinfunction "+_+") (pintype "passive"))
      (node (ref "IC8") (pin "8") (pinfunction "IN_8") (pintype "input"))
      (node (ref "R55") (pin "A") (pinfunction "A_A") (pintype "passive"))
      (node (ref "R55") (pin "S") (pinfunction "S_S") (pintype "passive"))
    )
    (net (code "120") (name "Net-(IC8-OUT)") (class "Default")
      (node (ref "C18") (pin "+") (pinfunction "+_+") (pintype "passive"))
      (node (ref "IC8") (pin "7") (pinfunction "OUT_7") (pintype "input"))
      (node (ref "R54") (pin "2") (pinfunction "2_2") (pintype "passive"))
    )
    (net (code "121") (name "Net-(IC9-D1)") (class "Default")
      (node (ref "IC9") (pin "1") (pinfunction "D1_1") (pintype "output"))
      (node (ref "SW8") (pin "1") (pinfunction "1_1") (pintype "passive"))
    )
    (net (code "122") (name "Net-(IC9-D2)") (class "Default")
      (node (ref "IC9") (pin "2") (pinfunction "D2_2") (pintype "output"))
      (node (ref "SW8") (pin "2") (pinfunction "2_2") (pintype "passive"))
    )
    (net (code "123") (name "Net-(IC9-D3)") (class "Default")
      (node (ref "IC9") (pin "3") (pinfunction "D3_3") (pintype "output"))
      (node (ref "SW8") (pin "3") (pinfunction "3_3") (pintype "passive"))
    )
    (net (code "124") (name "Net-(IC9-D4)") (class "Default")
      (node (ref "IC9") (pin "4") (pinfunction "D4_4") (pintype "output"))
      (node (ref "SW8") (pin "4") (pinfunction "4_4") (pintype "passive"))
    )
    (net (code "125") (name "Net-(IC9-D5)") (class "Default")
      (node (ref "IC9") (pin "6") (pinfunction "D5_6") (pintype "input"))
      (node (ref "SW8") (pin "5") (pinfunction "5_5") (pintype "passive"))
    )
    (net (code "126") (name "Net-(IC9-IN)") (class "Default")
      (node (ref "C21") (pin "+") (pinfunction "+_+") (pintype "passive"))
      (node (ref "IC9") (pin "8") (pinfunction "IN_8") (pintype "input"))
      (node (ref "R57") (pin "A") (pinfunction "A_A") (pintype "passive"))
      (node (ref "R57") (pin "S") (pinfunction "S_S") (pintype "passive"))
    )
    (net (code "127") (name "Net-(IC9-OUT)") (class "Default")
      (node (ref "C20") (pin "+") (pinfunction "+_+") (pintype "passive"))
      (node (ref "IC9") (pin "7") (pinfunction "OUT_7") (pintype "input"))
      (node (ref "R56") (pin "2") (pinfunction "2_2") (pintype "passive"))
    )
    (net (code "128") (name "Net-(IC10-D1)") (class "Default")
      (node (ref "IC10") (pin "1") (pinfunction "D1_1") (pintype "output"))
      (node (ref "SW9") (pin "1") (pinfunction "1_1") (pintype "passive"))
    )
    (net (code "129") (name "Net-(IC10-D2)") (class "Default")
      (node (ref "IC10") (pin "2") (pinfunction "D2_2") (pintype "output"))
      (node (ref "SW9") (pin "2") (pinfunction "2_2") (pintype "passive"))
    )
    (net (code "130") (name "Net-(IC10-D3)") (class "Default")
      (node (ref "IC10") (pin "3") (pinfunction "D3_3") (pintype "output"))
      (node (ref "SW9") (pin "3") (pinfunction "3_3") (pintype "passive"))
    )
    (net (code "131") (name "Net-(IC10-D4)") (class "Default")
      (node (ref "IC10") (pin "4") (pinfunction "D4_4") (pintype "output"))
      (node (ref "SW9") (pin "4") (pinfunction "4_4") (pintype "passive"))
    )
    (net (code "132") (name "Net-(IC10-D5)") (class "Default")
      (node (ref "IC10") (pin "6") (pinfunction "D5_6") (pintype "input"))
      (node (ref "SW9") (pin "5") (pinfunction "5_5") (pintype "passive"))
    )
    (net (code "133") (name "Net-(IC10-IN)") (class "Default")
      (node (ref "C23") (pin "+") (pinfunction "+_+") (pintype "passive"))
      (node (ref "IC10") (pin "8") (pinfunction "IN_8") (pintype "input"))
      (node (ref "R59") (pin "A") (pinfunction "A_A") (pintype "passive"))
      (node (ref "R59") (pin "S") (pinfunction "S_S") (pintype "passive"))
    )
    (net (code "134") (name "Net-(IC10-OUT)") (class "Default")
      (node (ref "C22") (pin "+") (pinfunction "+_+") (pintype "passive"))
      (node (ref "IC10") (pin "7") (pinfunction "OUT_7") (pintype "input"))
      (node (ref "R58") (pin "2") (pinfunction "2_2") (pintype "passive"))
    )
    (net (code "135") (name "Net-(IC11-D1)") (class "Default")
      (node (ref "IC11") (pin "1") (pinfunction "D1_1") (pintype "output"))
      (node (ref "SW10") (pin "1") (pinfunction "1_1") (pintype "passive"))
    )
    (net (code "136") (name "Net-(IC11-D2)") (class "Default")
      (node (ref "IC11") (pin "2") (pinfunction "D2_2") (pintype "output"))
      (node (ref "SW10") (pin "2") (pinfunction "2_2") (pintype "passive"))
    )
    (net (code "137") (name "Net-(IC11-D3)") (class "Default")
      (node (ref "IC11") (pin "3") (pinfunction "D3_3") (pintype "output"))
      (node (ref "SW10") (pin "3") (pinfunction "3_3") (pintype "passive"))
    )
    (net (code "138") (name "Net-(IC11-D4)") (class "Default")
      (node (ref "IC11") (pin "4") (pinfunction "D4_4") (pintype "output"))
      (node (ref "SW10") (pin "4") (pinfunction "4_4") (pintype "passive"))
    )
    (net (code "139") (name "Net-(IC11-D5)") (class "Default")
      (node (ref "IC11") (pin "6") (pinfunction "D5_6") (pintype "input"))
      (node (ref "SW10") (pin "5") (pinfunction "5_5") (pintype "passive"))
    )
    (net (code "140") (name "Net-(IC11-IN)") (class "Default")
      (node (ref "C25") (pin "+") (pinfunction "+_+") (pintype "passive"))
      (node (ref "IC11") (pin "8") (pinfunction "IN_8") (pintype "input"))
      (node (ref "R61") (pin "A") (pinfunction "A_A") (pintype "passive"))
      (node (ref "R61") (pin "S") (pinfunction "S_S") (pintype "passive"))
    )
    (net (code "141") (name "Net-(IC11-OUT)") (class "Default")
      (node (ref "C24") (pin "+") (pinfunction "+_+") (pintype "passive"))
      (node (ref "IC11") (pin "7") (pinfunction "OUT_7") (pintype "input"))
      (node (ref "R60") (pin "2") (pinfunction "2_2") (pintype "passive"))
    )
    (net (code "142") (name "Net-(IC12-D1)") (class "Default")
      (node (ref "IC12") (pin "1") (pinfunction "D1_1") (pintype "output"))
      (node (ref "SW11") (pin "1") (pinfunction "1_1") (pintype "passive"))
    )
    (net (code "143") (name "Net-(IC12-D2)") (class "Default")
      (node (ref "IC12") (pin "2") (pinfunction "D2_2") (pintype "output"))
      (node (ref "SW11") (pin "2") (pinfunction "2_2") (pintype "passive"))
    )
    (net (code "144") (name "Net-(IC12-D3)") (class "Default")
      (node (ref "IC12") (pin "3") (pinfunction "D3_3") (pintype "output"))
      (node (ref "SW11") (pin "3") (pinfunction "3_3") (pintype "passive"))
    )
    (net (code "145") (name "Net-(IC12-D4)") (class "Default")
      (node (ref "IC12") (pin "4") (pinfunction "D4_4") (pintype "output"))
      (node (ref "SW11") (pin "4") (pinfunction "4_4") (pintype "passive"))
    )
    (net (code "146") (name "Net-(IC12-D5)") (class "Default")
      (node (ref "IC12") (pin "6") (pinfunction "D5_6") (pintype "input"))
      (node (ref "SW11") (pin "5") (pinfunction "5_5") (pintype "passive"))
    )
    (net (code "147") (name "Net-(IC12-IN)") (class "Default")
      (node (ref "C27") (pin "+") (pinfunction "+_+") (pintype "passive"))
      (node (ref "IC12") (pin "8") (pinfunction "IN_8") (pintype "input"))
      (node (ref "R63") (pin "A") (pinfunction "A_A") (pintype "passive"))
      (node (ref "R63") (pin "S") (pinfunction "S_S") (pintype "passive"))
    )
    (net (code "148") (name "Net-(IC12-OUT)") (class "Default")
      (node (ref "C26") (pin "+") (pinfunction "+_+") (pintype "passive"))
      (node (ref "IC12") (pin "7") (pinfunction "OUT_7") (pintype "input"))
      (node (ref "R62") (pin "2") (pinfunction "2_2") (pintype "passive"))
    )
    (net (code "149") (name "Net-(IC13-D1)") (class "Default")
      (node (ref "IC13") (pin "1") (pinfunction "D1_1") (pintype "output"))
      (node (ref "SW12") (pin "1") (pinfunction "1_1") (pintype "passive"))
    )
    (net (code "150") (name "Net-(IC13-D2)") (class "Default")
      (node (ref "IC13") (pin "2") (pinfunction "D2_2") (pintype "output"))
      (node (ref "SW12") (pin "2") (pinfunction "2_2") (pintype "passive"))
    )
    (net (code "151") (name "Net-(IC13-D3)") (class "Default")
      (node (ref "IC13") (pin "3") (pinfunction "D3_3") (pintype "output"))
      (node (ref "SW12") (pin "3") (pinfunction "3_3") (pintype "passive"))
    )
    (net (code "152") (name "Net-(IC13-D4)") (class "Default")
      (node (ref "IC13") (pin "4") (pinfunction "D4_4") (pintype "output"))
      (node (ref "SW12") (pin "4") (pinfunction "4_4") (pintype "passive"))
    )
    (net (code "153") (name "Net-(IC13-D5)") (class "Default")
      (node (ref "IC13") (pin "6") (pinfunction "D5_6") (pintype "input"))
      (node (ref "SW12") (pin "5") (pinfunction "5_5") (pintype "passive"))
    )
    (net (code "154") (name "Net-(IC13-IN)") (class "Default")
      (node (ref "C29") (pin "+") (pinfunction "+_+") (pintype "passive"))
      (node (ref "IC13") (pin "8") (pinfunction "IN_8") (pintype "input"))
      (node (ref "R65") (pin "A") (pinfunction "A_A") (pintype "passive"))
      (node (ref "R65") (pin "S") (pinfunction "S_S") (pintype "passive"))
    )
    (net (code "155") (name "Net-(IC13-OUT)") (class "Default")
      (node (ref "C28") (pin "+") (pinfunction "+_+") (pintype "passive"))
      (node (ref "IC13") (pin "7") (pinfunction "OUT_7") (pintype "input"))
      (node (ref "R64") (pin "2") (pinfunction "2_2") (pintype "passive"))
    )
    (net (code "156") (name "Net-(IC14-D1)") (class "Default")
      (node (ref "IC14") (pin "1") (pinfunction "D1_1") (pintype "output"))
      (node (ref "SW13") (pin "1") (pinfunction "1_1") (pintype "passive"))
    )
    (net (code "157") (name "Net-(IC14-D2)") (class "Default")
      (node (ref "IC14") (pin "2") (pinfunction "D2_2") (pintype "output"))
      (node (ref "SW13") (pin "2") (pinfunction "2_2") (pintype "passive"))
    )
    (net (code "158") (name "Net-(IC14-D3)") (class "Default")
      (node (ref "IC14") (pin "3") (pinfunction "D3_3") (pintype "output"))
      (node (ref "SW13") (pin "3") (pinfunction "3_3") (pintype "passive"))
    )
    (net (code "159") (name "Net-(IC14-D4)") (class "Default")
      (node (ref "IC14") (pin "4") (pinfunction "D4_4") (pintype "output"))
      (node (ref "SW13") (pin "4") (pinfunction "4_4") (pintype "passive"))
    )
    (net (code "160") (name "Net-(IC14-D5)") (class "Default")
      (node (ref "IC14") (pin "6") (pinfunction "D5_6") (pintype "input"))
      (node (ref "SW13") (pin "5") (pinfunction "5_5") (pintype "passive"))
    )
    (net (code "161") (name "Net-(IC14-IN)") (class "Default")
      (node (ref "C31") (pin "+") (pinfunction "+_+") (pintype "passive"))
      (node (ref "IC14") (pin "8") (pinfunction "IN_8") (pintype "input"))
      (node (ref "R67") (pin "A") (pinfunction "A_A") (pintype "passive"))
      (node (ref "R67") (pin "S") (pinfunction "S_S") (pintype "passive"))
    )
    (net (code "162") (name "Net-(IC14-OUT)") (class "Default")
      (node (ref "C30") (pin "+") (pinfunction "+_+") (pintype "passive"))
      (node (ref "IC14") (pin "7") (pinfunction "OUT_7") (pintype "input"))
      (node (ref "R66") (pin "2") (pinfunction "2_2") (pintype "passive"))
    )
    (net (code "163") (name "Net-(IC15-D1)") (class "Default")
      (node (ref "IC15") (pin "1") (pinfunction "D1_1") (pintype "output"))
      (node (ref "SW14") (pin "1") (pinfunction "1_1") (pintype "passive"))
    )
    (net (code "164") (name "Net-(IC15-D2)") (class "Default")
      (node (ref "IC15") (pin "2") (pinfunction "D2_2") (pintype "output"))
      (node (ref "SW14") (pin "2") (pinfunction "2_2") (pintype "passive"))
    )
    (net (code "165") (name "Net-(IC15-D3)") (class "Default")
      (node (ref "IC15") (pin "3") (pinfunction "D3_3") (pintype "output"))
      (node (ref "SW14") (pin "3") (pinfunction "3_3") (pintype "passive"))
    )
    (net (code "166") (name "Net-(IC15-D4)") (class "Default")
      (node (ref "IC15") (pin "4") (pinfunction "D4_4") (pintype "output"))
      (node (ref "SW14") (pin "4") (pinfunction "4_4") (pintype "passive"))
    )
    (net (code "167") (name "Net-(IC15-D5)") (class "Default")
      (node (ref "IC15") (pin "6") (pinfunction "D5_6") (pintype "input"))
      (node (ref "SW14") (pin "5") (pinfunction "5_5") (pintype "passive"))
    )
    (net (code "168") (name "Net-(IC15-IN)") (class "Default")
      (node (ref "C33") (pin "+") (pinfunction "+_+") (pintype "passive"))
      (node (ref "IC15") (pin "8") (pinfunction "IN_8") (pintype "input"))
      (node (ref "R69") (pin "A") (pinfunction "A_A") (pintype "passive"))
      (node (ref "R69") (pin "S") (pinfunction "S_S") (pintype "passive"))
    )
    (net (code "169") (name "Net-(IC15-OUT)") (class "Default")
      (node (ref "C32") (pin "+") (pinfunction "+_+") (pintype "passive"))
      (node (ref "IC15") (pin "7") (pinfunction "OUT_7") (pintype "input"))
      (node (ref "R68") (pin "2") (pinfunction "2_2") (pintype "passive"))
    )
    (net (code "170") (name "Net-(IC16-D1)") (class "Default")
      (node (ref "IC16") (pin "1") (pinfunction "D1_1") (pintype "output"))
      (node (ref "SW15") (pin "1") (pinfunction "1_1") (pintype "passive"))
    )
    (net (code "171") (name "Net-(IC16-D2)") (class "Default")
      (node (ref "IC16") (pin "2") (pinfunction "D2_2") (pintype "output"))
      (node (ref "SW15") (pin "2") (pinfunction "2_2") (pintype "passive"))
    )
    (net (code "172") (name "Net-(IC16-D3)") (class "Default")
      (node (ref "IC16") (pin "3") (pinfunction "D3_3") (pintype "output"))
      (node (ref "SW15") (pin "3") (pinfunction "3_3") (pintype "passive"))
    )
    (net (code "173") (name "Net-(IC16-D4)") (class "Default")
      (node (ref "IC16") (pin "4") (pinfunction "D4_4") (pintype "output"))
      (node (ref "SW15") (pin "4") (pinfunction "4_4") (pintype "passive"))
    )
    (net (code "174") (name "Net-(IC16-D5)") (class "Default")
      (node (ref "IC16") (pin "6") (pinfunction "D5_6") (pintype "input"))
      (node (ref "SW15") (pin "5") (pinfunction "5_5") (pintype "passive"))
    )
    (net (code "175") (name "Net-(IC16-IN)") (class "Default")
      (node (ref "C35") (pin "+") (pinfunction "+_+") (pintype "passive"))
      (node (ref "IC16") (pin "8") (pinfunction "IN_8") (pintype "input"))
      (node (ref "R71") (pin "A") (pinfunction "A_A") (pintype "passive"))
      (node (ref "R71") (pin "S") (pinfunction "S_S") (pintype "passive"))
    )
    (net (code "176") (name "Net-(IC16-OUT)") (class "Default")
      (node (ref "C34") (pin "+") (pinfunction "+_+") (pintype "passive"))
      (node (ref "IC16") (pin "7") (pinfunction "OUT_7") (pintype "input"))
      (node (ref "R70") (pin "2") (pinfunction "2_2") (pintype "passive"))
    )
    (net (code "177") (name "Net-(IC17-D1)") (class "Default")
      (node (ref "IC17") (pin "1") (pinfunction "D1_1") (pintype "output"))
      (node (ref "SW16") (pin "1") (pinfunction "1_1") (pintype "passive"))
    )
    (net (code "178") (name "Net-(IC17-D2)") (class "Default")
      (node (ref "IC17") (pin "2") (pinfunction "D2_2") (pintype "output"))
      (node (ref "SW16") (pin "2") (pinfunction "2_2") (pintype "passive"))
    )
    (net (code "179") (name "Net-(IC17-D3)") (class "Default")
      (node (ref "IC17") (pin "3") (pinfunction "D3_3") (pintype "output"))
      (node (ref "SW16") (pin "3") (pinfunction "3_3") (pintype "passive"))
    )
    (net (code "180") (name "Net-(IC17-D4)") (class "Default")
      (node (ref "IC17") (pin "4") (pinfunction "D4_4") (pintype "output"))
      (node (ref "SW16") (pin "4") (pinfunction "4_4") (pintype "passive"))
    )
    (net (code "181") (name "Net-(IC17-D5)") (class "Default")
      (node (ref "IC17") (pin "6") (pinfunction "D5_6") (pintype "input"))
      (node (ref "SW16") (pin "5") (pinfunction "5_5") (pintype "passive"))
    )
    (net (code "182") (name "Net-(IC17-IN)") (class "Default")
      (node (ref "C37") (pin "+") (pinfunction "+_+") (pintype "passive"))
      (node (ref "IC17") (pin "8") (pinfunction "IN_8") (pintype "input"))
      (node (ref "R73") (pin "A") (pinfunction "A_A") (pintype "passive"))
      (node (ref "R73") (pin "S") (pinfunction "S_S") (pintype "passive"))
    )
    (net (code "183") (name "Net-(IC17-OUT)") (class "Default")
      (node (ref "C36") (pin "+") (pinfunction "+_+") (pintype "passive"))
      (node (ref "IC17") (pin "7") (pinfunction "OUT_7") (pintype "input"))
      (node (ref "R72") (pin "2") (pinfunction "2_2") (pintype "passive"))
    )
    (net (code "184") (name "Net-(IC18-D1)") (class "Default")
      (node (ref "IC18") (pin "1") (pinfunction "D1_1") (pintype "output"))
      (node (ref "SW17") (pin "1") (pinfunction "1_1") (pintype "passive"))
    )
    (net (code "185") (name "Net-(IC18-D2)") (class "Default")
      (node (ref "IC18") (pin "2") (pinfunction "D2_2") (pintype "output"))
      (node (ref "SW17") (pin "2") (pinfunction "2_2") (pintype "passive"))
    )
    (net (code "186") (name "Net-(IC18-D3)") (class "Default")
      (node (ref "IC18") (pin "3") (pinfunction "D3_3") (pintype "output"))
      (node (ref "SW17") (pin "3") (pinfunction "3_3") (pintype "passive"))
    )
    (net (code "187") (name "Net-(IC18-D4)") (class "Default")
      (node (ref "IC18") (pin "4") (pinfunction "D4_4") (pintype "output"))
      (node (ref "SW17") (pin "4") (pinfunction "4_4") (pintype "passive"))
    )
    (net (code "188") (name "Net-(IC18-D5)") (class "Default")
      (node (ref "IC18") (pin "6") (pinfunction "D5_6") (pintype "input"))
      (node (ref "SW17") (pin "5") (pinfunction "5_5") (pintype "passive"))
    )
    (net (code "189") (name "Net-(IC18-IN)") (class "Default")
      (node (ref "C39") (pin "+") (pinfunction "+_+") (pintype "passive"))
      (node (ref "IC18") (pin "8") (pinfunction "IN_8") (pintype "input"))
      (node (ref "R75") (pin "A") (pinfunction "A_A") (pintype "passive"))
      (node (ref "R75") (pin "S") (pinfunction "S_S") (pintype "passive"))
    )
    (net (code "190") (name "Net-(IC18-OUT)") (class "Default")
      (node (ref "C38") (pin "+") (pinfunction "+_+") (pintype "passive"))
      (node (ref "IC18") (pin "7") (pinfunction "OUT_7") (pintype "input"))
      (node (ref "R74") (pin "2") (pinfunction "2_2") (pintype "passive"))
    )
    (net (code "191") (name "Net-(IC19-D1)") (class "Default")
      (node (ref "IC19") (pin "1") (pinfunction "D1_1") (pintype "output"))
      (node (ref "SW18") (pin "1") (pinfunction "1_1") (pintype "passive"))
    )
    (net (code "192") (name "Net-(IC19-D2)") (class "Default")
      (node (ref "IC19") (pin "2") (pinfunction "D2_2") (pintype "output"))
      (node (ref "SW18") (pin "2") (pinfunction "2_2") (pintype "passive"))
    )
    (net (code "193") (name "Net-(IC19-D3)") (class "Default")
      (node (ref "IC19") (pin "3") (pinfunction "D3_3") (pintype "output"))
      (node (ref "SW18") (pin "3") (pinfunction "3_3") (pintype "passive"))
    )
    (net (code "194") (name "Net-(IC19-D4)") (class "Default")
      (node (ref "IC19") (pin "4") (pinfunction "D4_4") (pintype "output"))
      (node (ref "SW18") (pin "4") (pinfunction "4_4") (pintype "passive"))
    )
    (net (code "195") (name "Net-(IC19-D5)") (class "Default")
      (node (ref "IC19") (pin "6") (pinfunction "D5_6") (pintype "input"))
      (node (ref "SW18") (pin "5") (pinfunction "5_5") (pintype "passive"))
    )
    (net (code "196") (name "Net-(IC19-IN)") (class "Default")
      (node (ref "C41") (pin "+") (pinfunction "+_+") (pintype "passive"))
      (node (ref "IC19") (pin "8") (pinfunction "IN_8") (pintype "input"))
      (node (ref "R77") (pin "A") (pinfunction "A_A") (pintype "passive"))
      (node (ref "R77") (pin "S") (pinfunction "S_S") (pintype "passive"))
    )
    (net (code "197") (name "Net-(IC19-OUT)") (class "Default")
      (node (ref "C40") (pin "+") (pinfunction "+_+") (pintype "passive"))
      (node (ref "IC19") (pin "7") (pinfunction "OUT_7") (pintype "input"))
      (node (ref "R76") (pin "2") (pinfunction "2_2") (pintype "passive"))
    )
    (net (code "198") (name "Net-(IC20-D1)") (class "Default")
      (node (ref "IC20") (pin "1") (pinfunction "D1_1") (pintype "output"))
      (node (ref "SW19") (pin "1") (pinfunction "1_1") (pintype "passive"))
    )
    (net (code "199") (name "Net-(IC20-D2)") (class "Default")
      (node (ref "IC20") (pin "2") (pinfunction "D2_2") (pintype "output"))
      (node (ref "SW19") (pin "2") (pinfunction "2_2") (pintype "passive"))
    )
    (net (code "200") (name "Net-(IC20-D3)") (class "Default")
      (node (ref "IC20") (pin "3") (pinfunction "D3_3") (pintype "output"))
      (node (ref "SW19") (pin "3") (pinfunction "3_3") (pintype "passive"))
    )
    (net (code "201") (name "Net-(IC20-D4)") (class "Default")
      (node (ref "IC20") (pin "4") (pinfunction "D4_4") (pintype "output"))
      (node (ref "SW19") (pin "4") (pinfunction "4_4") (pintype "passive"))
    )
    (net (code "202") (name "Net-(IC20-D5)") (class "Default")
      (node (ref "IC20") (pin "6") (pinfunction "D5_6") (pintype "input"))
      (node (ref "SW19") (pin "5") (pinfunction "5_5") (pintype "passive"))
    )
    (net (code "203") (name "Net-(IC20-IN)") (class "Default")
      (node (ref "C43") (pin "+") (pinfunction "+_+") (pintype "passive"))
      (node (ref "IC20") (pin "8") (pinfunction "IN_8") (pintype "input"))
      (node (ref "R79") (pin "A") (pinfunction "A_A") (pintype "passive"))
      (node (ref "R79") (pin "S") (pinfunction "S_S") (pintype "passive"))
    )
    (net (code "204") (name "Net-(IC20-OUT)") (class "Default")
      (node (ref "C42") (pin "+") (pinfunction "+_+") (pintype "passive"))
      (node (ref "IC20") (pin "7") (pinfunction "OUT_7") (pintype "input"))
      (node (ref "R78") (pin "2") (pinfunction "2_2") (pintype "passive"))
    )
    (net (code "205") (name "Net-(IC21-D1)") (class "Default")
      (node (ref "IC21") (pin "1") (pinfunction "D1_1") (pintype "output"))
      (node (ref "SW20") (pin "1") (pinfunction "1_1") (pintype "passive"))
    )
    (net (code "206") (name "Net-(IC21-D2)") (class "Default")
      (node (ref "IC21") (pin "2") (pinfunction "D2_2") (pintype "output"))
      (node (ref "SW20") (pin "2") (pinfunction "2_2") (pintype "passive"))
    )
    (net (code "207") (name "Net-(IC21-D3)") (class "Default")
      (node (ref "IC21") (pin "3") (pinfunction "D3_3") (pintype "output"))
      (node (ref "SW20") (pin "3") (pinfunction "3_3") (pintype "passive"))
    )
    (net (code "208") (name "Net-(IC21-D4)") (class "Default")
      (node (ref "IC21") (pin "4") (pinfunction "D4_4") (pintype "output"))
      (node (ref "SW20") (pin "4") (pinfunction "4_4") (pintype "passive"))
    )
    (net (code "209") (name "Net-(IC21-D5)") (class "Default")
      (node (ref "IC21") (pin "6") (pinfunction "D5_6") (pintype "input"))
      (node (ref "SW20") (pin "5") (pinfunction "5_5") (pintype "passive"))
    )
    (net (code "210") (name "Net-(IC21-IN)") (class "Default")
      (node (ref "C45") (pin "+") (pinfunction "+_+") (pintype "passive"))
      (node (ref "IC21") (pin "8") (pinfunction "IN_8") (pintype "input"))
      (node (ref "R81") (pin "A") (pinfunction "A_A") (pintype "passive"))
      (node (ref "R81") (pin "S") (pinfunction "S_S") (pintype "passive"))
    )
    (net (code "211") (name "Net-(IC21-OUT)") (class "Default")
      (node (ref "C44") (pin "+") (pinfunction "+_+") (pintype "passive"))
      (node (ref "IC21") (pin "7") (pinfunction "OUT_7") (pintype "input"))
      (node (ref "R80") (pin "2") (pinfunction "2_2") (pintype "passive"))
    )
    (net (code "212") (name "Net-(IC22-GND)") (class "Default")
      (node (ref "C46") (pin "-") (pinfunction "-_-") (pintype "passive"))
      (node (ref "C47") (pin "2") (pinfunction "2_2") (pintype "passive"))
      (node (ref "IC22") (pin "2") (pinfunction "GND_2") (pintype "passive"))
      (node (ref "J1") (pin "1") (pinfunction "1_1") (pintype "passive"))
      (node (ref "R82") (pin "2") (pinfunction "2_2") (pintype "passive"))
    )
    (net (code "213") (name "Net-(IC22-VI)") (class "Default")
      (node (ref "C46") (pin "+") (pinfunction "+_+") (pintype "passive"))
      (node (ref "C47") (pin "1") (pinfunction "1_1") (pintype "passive"))
      (node (ref "D1") (pin "C") (pinfunction "C_C") (pintype "passive"))
      (node (ref "IC22") (pin "1") (pinfunction "VI_1") (pintype "input"))
    )
    (net (code "214") (name "Net-(JP1-Pad1)") (class "Default")
      (node (ref "JP1") (pin "1") (pinfunction "1_1") (pintype "passive"))
      (node (ref "LED1") (pin "A") (pinfunction "A_A") (pintype "passive"))
    )
    (net (code "215") (name "Net-(JP1-Pad2)") (class "Default")
      (node (ref "JP1") (pin "2") (pinfunction "2_2") (pintype "passive"))
      (node (ref "R83") (pin "1") (pinfunction "1_1") (pintype "passive"))
    )
    (net (code "216") (name "Net-(OK1-A)") (class "Default")
      (node (ref "OK1") (pin "1") (pinfunction "A_1") (pintype "passive"))
      (node (ref "R2") (pin "1") (pinfunction "1_1") (pintype "passive"))
    )
    (net (code "217") (name "Net-(OK2-A)") (class "Default")
      (node (ref "OK2") (pin "1") (pinfunction "A_1") (pintype "passive"))
      (node (ref "R4") (pin "1") (pinfunction "1_1") (pintype "passive"))
    )
    (net (code "218") (name "Net-(OK3-A)") (class "Default")
      (node (ref "OK3") (pin "1") (pinfunction "A_1") (pintype "passive"))
      (node (ref "R6") (pin "1") (pinfunction "1_1") (pintype "passive"))
    )
    (net (code "219") (name "Net-(OK4-A)") (class "Default")
      (node (ref "OK4") (pin "1") (pinfunction "A_1") (pintype "passive"))
      (node (ref "R8") (pin "1") (pinfunction "1_1") (pintype "passive"))
    )
    (net (code "220") (name "Net-(OK5-A)") (class "Default")
      (node (ref "OK5") (pin "1") (pinfunction "A_1") (pintype "passive"))
      (node (ref "R10") (pin "1") (pinfunction "1_1") (pintype "passive"))
    )
    (net (code "221") (name "Net-(OK6-A)") (class "Default")
      (node (ref "OK6") (pin "1") (pinfunction "A_1") (pintype "passive"))
      (node (ref "R12") (pin "1") (pinfunction "1_1") (pintype "passive"))
    )
    (net (code "222") (name "Net-(OK7-A)") (class "Default")
      (node (ref "OK7") (pin "1") (pinfunction "A_1") (pintype "passive"))
      (node (ref "R14") (pin "1") (pinfunction "1_1") (pintype "passive"))
    )
    (net (code "223") (name "Net-(OK8-A)") (class "Default")
      (node (ref "OK8") (pin "1") (pinfunction "A_1") (pintype "passive"))
      (node (ref "R16") (pin "1") (pinfunction "1_1") (pintype "passive"))
    )
    (net (code "224") (name "Net-(OK9-A)") (class "Default")
      (node (ref "OK9") (pin "1") (pinfunction "A_1") (pintype "passive"))
      (node (ref "R18") (pin "1") (pinfunction "1_1") (pintype "passive"))
    )
    (net (code "225") (name "Net-(OK10-A)") (class "Default")
      (node (ref "OK10") (pin "1") (pinfunction "A_1") (pintype "passive"))
      (node (ref "R20") (pin "1") (pinfunction "1_1") (pintype "passive"))
    )
    (net (code "226") (name "Net-(OK11-A)") (class "Default")
      (node (ref "OK11") (pin "1") (pinfunction "A_1") (pintype "passive"))
      (node (ref "R22") (pin "1") (pinfunction "1_1") (pintype "passive"))
    )
    (net (code "227") (name "Net-(OK12-A)") (class "Default")
      (node (ref "OK12") (pin "1") (pinfunction "A_1") (pintype "passive"))
      (node (ref "R24") (pin "1") (pinfunction "1_1") (pintype "passive"))
    )
    (net (code "228") (name "Net-(OK13-A)") (class "Default")
      (node (ref "OK13") (pin "1") (pinfunction "A_1") (pintype "passive"))
      (node (ref "R26") (pin "1") (pinfunction "1_1") (pintype "passive"))
    )
    (net (code "229") (name "Net-(OK14-A)") (class "Default")
      (node (ref "OK14") (pin "1") (pinfunction "A_1") (pintype "passive"))
      (node (ref "R28") (pin "1") (pinfunction "1_1") (pintype "passive"))
    )
    (net (code "230") (name "Net-(OK15-A)") (class "Default")
      (node (ref "OK15") (pin "1") (pinfunction "A_1") (pintype "passive"))
      (node (ref "R30") (pin "1") (pinfunction "1_1") (pintype "passive"))
    )
    (net (code "231") (name "Net-(OK16-A)") (class "Default")
      (node (ref "OK16") (pin "1") (pinfunction "A_1") (pintype "passive"))
      (node (ref "R32") (pin "1") (pinfunction "1_1") (pintype "passive"))
    )
    (net (code "232") (name "Net-(OK17-A)") (class "Default")
      (node (ref "OK17") (pin "1") (pinfunction "A_1") (pintype "passive"))
      (node (ref "R34") (pin "1") (pinfunction "1_1") (pintype "passive"))
    )
    (net (code "233") (name "Net-(OK18-A)") (class "Default")
      (node (ref "OK18") (pin "1") (pinfunction "A_1") (pintype "passive"))
      (node (ref "R36") (pin "1") (pinfunction "1_1") (pintype "passive"))
    )
    (net (code "234") (name "Net-(OK19-A)") (class "Default")
      (node (ref "OK19") (pin "1") (pinfunction "A_1") (pintype "passive"))
      (node (ref "R38") (pin "1") (pinfunction "1_1") (pintype "passive"))
    )
    (net (code "235") (name "Net-(OK20-A)") (class "Default")
      (node (ref "OK20") (pin "1") (pinfunction "A_1") (pintype "passive"))
      (node (ref "R40") (pin "1") (pinfunction "1_1") (pintype "passive"))
    )
    (net (code "236") (name "unconnected-(IC1-RC0{slash}TIOSO{slash}T13CKI-Pad15)") (class "Default")
      (node (ref "IC1") (pin "15") (pinfunction "RC0/TIOSO/T13CKI_15") (pintype "bidirectional"))
    )
    (net (code "237") (name "unconnected-(IC1-RC1{slash}T1OSI{slash}ICCP2{slash}~{UOE}-Pad16)") (class "Default")
      (node (ref "IC1") (pin "16") (pinfunction "RC1/T1OSI/ICCP2/~{UOE}_16") (pintype "bidirectional"))
    )
    (net (code "238") (name "unconnected-(IC1-RC2{slash}CCP1{slash}P1A-Pad17)") (class "Default")
      (node (ref "IC1") (pin "17") (pinfunction "RC2/CCP1/P1A_17") (pintype "bidirectional"))
    )
    (net (code "239") (name "unconnected-(IC1-RC6{slash}TX{slash}CK-Pad25)") (class "Default")
      (node (ref "IC1") (pin "25") (pinfunction "RC6/TX/CK_25") (pintype "bidirectional"))
    )
    (net (code "240") (name "unconnected-(IC1-RC7{slash}RX{slash}DT{slash}SDO-Pad26)") (class "Default")
      (node (ref "IC1") (pin "26") (pinfunction "RC7/RX/DT/SDO_26") (pintype "bidirectional"))
    )
    (net (code "241") (name "unconnected-(IC1-RE0{slash}AN5{slash}CK1SPP-Pad8)") (class "Default")
      (node (ref "IC1") (pin "8") (pinfunction "RE0/AN5/CK1SPP_8") (pintype "bidirectional"))
    )
    (net (code "242") (name "unconnected-(IC1-RE1{slash}AN6{slash}CK2SPP-Pad9)") (class "Default")
      (node (ref "IC1") (pin "9") (pinfunction "RE1/AN6/CK2SPP_9") (pintype "bidirectional"))
    )
    (net (code "243") (name "unconnected-(IC1-RE2{slash}AN7{slash}OESPP-Pad10)") (class "Default")
      (node (ref "IC1") (pin "10") (pinfunction "RE2/AN7/OESPP_10") (pintype "bidirectional"))
    )
    (net (code "244") (name "unconnected-(J1-Pad2)") (class "Default")
      (node (ref "J1") (pin "2") (pinfunction "2_2") (pintype "passive"))
    )
  )
)
